# PIC24_sensores_esquem_tico-temp.net
KiCad netlist of a schematic drawn in Altium Designer
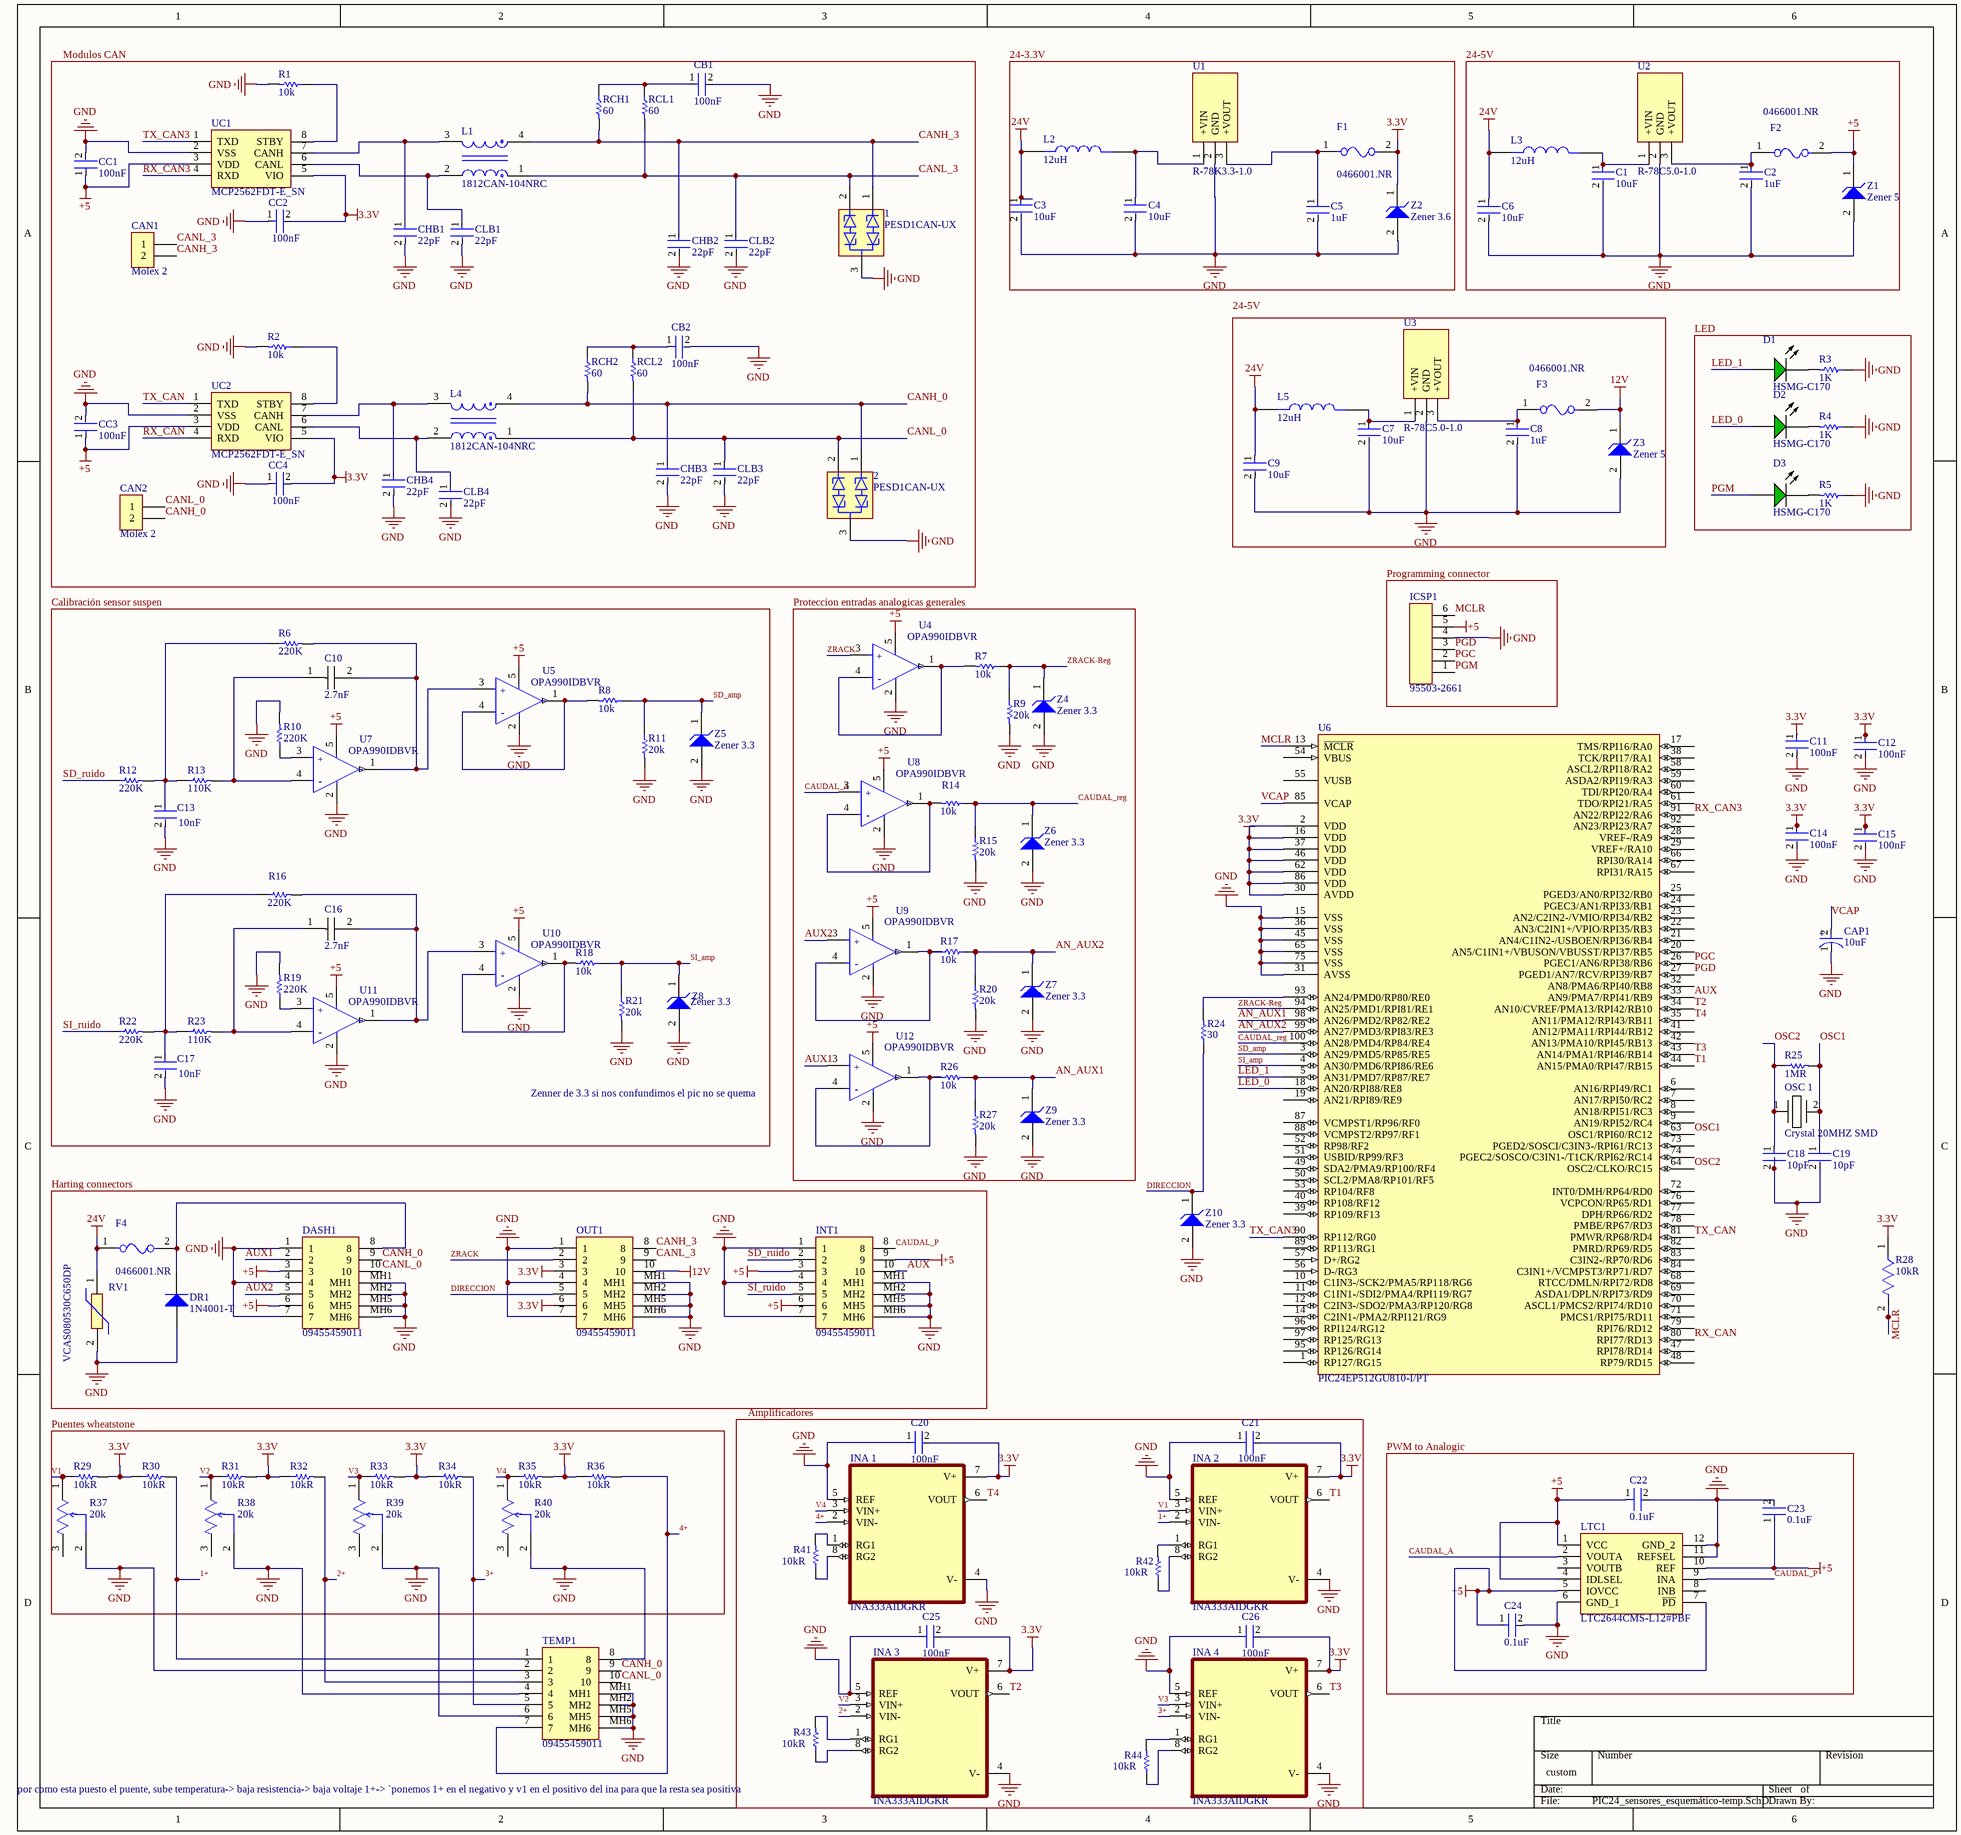
[diagram p0: PIC24_sensores_esquemático-temp.SchDoc]

(export (version "E")
  (design (tool "Eeschema 10.0.6"))
  (components
    (comp (ref "1")
      (value "PESD1CAN-UX")
      (footprint "FP-SOT323-MFG")
      (description "PESD1CAN Series 50 V 9.3 pF SMT CAN bus ESD Protection Diode - SOT-323")
      (libsource (lib "EMEA- Formula Student Team Bizkaia- University of the Basque Country") (part "04d57993b6b7b0f5b3c95ba4f97dea0"))
    )
    (comp (ref "2")
      (value "PESD1CAN-UX")
      (footprint "FP-SOT323-MFG")
      (description "PESD1CAN Series 50 V 9.3 pF SMT CAN bus ESD Protection Diode - SOT-323")
      (libsource (lib "EMEA- Formula Student Team Bizkaia- University of the Basque Country") (part "04d57993b6b7b0f5b3c95ba4f97dea0"))
    )
    (comp (ref "C1")
      (value "10uF")
      (footprint "FP-CL21-IPC_B")
      (description "Cap Ceramic 1uF 25V Y5V -20% to 80% SMD 0805 85°C Embossed T/R")
      (fields (field (name "TOLERANCE") "80%") (field (name "Comment") "CL21F105ZAFNNNF"))
      (libsource (lib "EMEA- Formula Student Team Bizkaia- University of the Basque Country") (part "b4654b650e69147ec39a6b967a45e02"))
    )
    (comp (ref "C2")
      (value "1uF")
      (footprint "FP-CL21-IPC_B")
      (description "Cap Ceramic 1uF 25V Y5V -20% to 80% SMD 0805 85°C Embossed T/R")
      (fields (field (name "TOLERANCE") "80%") (field (name "Comment") "CL21F105ZAFNNNF"))
      (libsource (lib "EMEA- Formula Student Team Bizkaia- University of the Basque Country") (part "b4654b650e69147ec39a6b967a45e02"))
    )
    (comp (ref "C3")
      (value "10uF")
      (footprint "FP-CL21-IPC_B")
      (description "Cap Ceramic 1uF 25V Y5V -20% to 80% SMD 0805 85°C Embossed T/R")
      (fields (field (name "TOLERANCE") "80%") (field (name "Comment") "CL21F105ZAFNNNF"))
      (libsource (lib "EMEA- Formula Student Team Bizkaia- University of the Basque Country") (part "b4654b650e69147ec39a6b967a45e02"))
    )
    (comp (ref "C4")
      (value "10uF")
      (footprint "FP-CL21-IPC_B")
      (description "Cap Ceramic 1uF 25V Y5V -20% to 80% SMD 0805 85°C Embossed T/R")
      (fields (field (name "TOLERANCE") "80%") (field (name "Comment") "CL21F105ZAFNNNF"))
      (libsource (lib "EMEA- Formula Student Team Bizkaia- University of the Basque Country") (part "b4654b650e69147ec39a6b967a45e02"))
    )
    (comp (ref "C5")
      (value "1uF")
      (footprint "FP-CL21-IPC_B")
      (description "Cap Ceramic 1uF 25V Y5V -20% to 80% SMD 0805 85°C Embossed T/R")
      (fields (field (name "TOLERANCE") "80%") (field (name "Comment") "CL21F105ZAFNNNF"))
      (libsource (lib "EMEA- Formula Student Team Bizkaia- University of the Basque Country") (part "b4654b650e69147ec39a6b967a45e02"))
    )
    (comp (ref "C6")
      (value "10uF")
      (footprint "FP-CL21-IPC_B")
      (description "Cap Ceramic 1uF 25V Y5V -20% to 80% SMD 0805 85°C Embossed T/R")
      (fields (field (name "TOLERANCE") "80%") (field (name "Comment") "CL21F105ZAFNNNF"))
      (libsource (lib "EMEA- Formula Student Team Bizkaia- University of the Basque Country") (part "b4654b650e69147ec39a6b967a45e02"))
    )
    (comp (ref "C7")
      (value "10uF")
      (footprint "FP-CL21-IPC_B")
      (description "Cap Ceramic 1uF 25V Y5V -20% to 80% SMD 0805 85°C Embossed T/R")
      (fields (field (name "TOLERANCE") "80%") (field (name "Comment") "CL21F105ZAFNNNF"))
      (libsource (lib "EMEA- Formula Student Team Bizkaia- University of the Basque Country") (part "b4654b650e69147ec39a6b967a45e02"))
    )
    (comp (ref "C8")
      (value "1uF")
      (footprint "FP-CL21-IPC_B")
      (description "Cap Ceramic 1uF 25V Y5V -20% to 80% SMD 0805 85°C Embossed T/R")
      (fields (field (name "TOLERANCE") "80%") (field (name "Comment") "CL21F105ZAFNNNF"))
      (libsource (lib "EMEA- Formula Student Team Bizkaia- University of the Basque Country") (part "b4654b650e69147ec39a6b967a45e02"))
    )
    (comp (ref "C9")
      (value "10uF")
      (footprint "FP-CL21-IPC_B")
      (description "Cap Ceramic 1uF 25V Y5V -20% to 80% SMD 0805 85°C Embossed T/R")
      (fields (field (name "TOLERANCE") "80%") (field (name "Comment") "CL21F105ZAFNNNF"))
      (libsource (lib "EMEA- Formula Student Team Bizkaia- University of the Basque Country") (part "b4654b650e69147ec39a6b967a45e02"))
    )
    (comp (ref "C10")
      (value "2.7nF")
      (footprint "TMK212BJ105KG-T-Footprint-1")
      (description "0805 1 uF 25 V ±10 % X5R Surface Mount Multilayer Ceramic Capacitor")
      (fields (field (name "TOLERANCE") "10%"))
      (libsource (lib "EMEA- Formula Student Team Bizkaia- University of the Basque Country") (part "TMK212BJ105KG-T-Symbol-1"))
    )
    (comp (ref "C11")
      (value "100nF")
      (footprint "FP-CL21-IPC_B")
      (description "Cap Ceramic 1uF 25V Y5V -20% to 80% SMD 0805 85°C Embossed T/R")
      (fields (field (name "TOLERANCE") "80%") (field (name "Comment") "CL21F105ZAFNNNF"))
      (libsource (lib "EMEA- Formula Student Team Bizkaia- University of the Basque Country") (part "b4654b650e69147ec39a6b967a45e02"))
    )
    (comp (ref "C12")
      (value "100nF")
      (footprint "FP-CL21-IPC_B")
      (description "Cap Ceramic 1uF 25V Y5V -20% to 80% SMD 0805 85°C Embossed T/R")
      (fields (field (name "TOLERANCE") "80%") (field (name "Comment") "CL21F105ZAFNNNF"))
      (libsource (lib "EMEA- Formula Student Team Bizkaia- University of the Basque Country") (part "b4654b650e69147ec39a6b967a45e02"))
    )
    (comp (ref "C13")
      (value "10nF")
      (footprint "FP-CL21-IPC_B")
      (description "Cap Ceramic 1uF 25V Y5V -20% to 80% SMD 0805 85°C Embossed T/R")
      (fields (field (name "TOLERANCE") "80%") (field (name "Comment") "CL21F105ZAFNNNF"))
      (libsource (lib "EMEA- Formula Student Team Bizkaia- University of the Basque Country") (part "b4654b650e69147ec39a6b967a45e02"))
    )
    (comp (ref "C14")
      (value "100nF")
      (footprint "FP-CL21-IPC_B")
      (description "Cap Ceramic 1uF 25V Y5V -20% to 80% SMD 0805 85°C Embossed T/R")
      (fields (field (name "TOLERANCE") "80%") (field (name "Comment") "CL21F105ZAFNNNF"))
      (libsource (lib "EMEA- Formula Student Team Bizkaia- University of the Basque Country") (part "b4654b650e69147ec39a6b967a45e02"))
    )
    (comp (ref "C15")
      (value "100nF")
      (footprint "FP-CL21-IPC_B")
      (description "Cap Ceramic 1uF 25V Y5V -20% to 80% SMD 0805 85°C Embossed T/R")
      (fields (field (name "TOLERANCE") "80%") (field (name "Comment") "CL21F105ZAFNNNF"))
      (libsource (lib "EMEA- Formula Student Team Bizkaia- University of the Basque Country") (part "b4654b650e69147ec39a6b967a45e02"))
    )
    (comp (ref "C16")
      (value "2.7nF")
      (footprint "TMK212BJ105KG-T-Footprint-1")
      (description "0805 1 uF 25 V ±10 % X5R Surface Mount Multilayer Ceramic Capacitor")
      (fields (field (name "TOLERANCE") "10%"))
      (libsource (lib "EMEA- Formula Student Team Bizkaia- University of the Basque Country") (part "TMK212BJ105KG-T-Symbol-1"))
    )
    (comp (ref "C17")
      (value "10nF")
      (footprint "FP-CL21-IPC_B")
      (description "Cap Ceramic 1uF 25V Y5V -20% to 80% SMD 0805 85°C Embossed T/R")
      (fields (field (name "TOLERANCE") "80%") (field (name "Comment") "CL21F105ZAFNNNF"))
      (libsource (lib "EMEA- Formula Student Team Bizkaia- University of the Basque Country") (part "b4654b650e69147ec39a6b967a45e02"))
    )
    (comp (ref "C18")
      (value "10pF")
      (footprint "FP-CL21-IPC_B")
      (description "Cap Ceramic 1uF 25V Y5V -20% to 80% SMD 0805 85°C Embossed T/R")
      (fields (field (name "TOLERANCE") "80%") (field (name "Comment") "CL21F105ZAFNNNF"))
      (libsource (lib "EMEA- Formula Student Team Bizkaia- University of the Basque Country") (part "b4654b650e69147ec39a6b967a45e02"))
    )
    (comp (ref "C19")
      (value "10pF")
      (footprint "FP-CL21-IPC_B")
      (description "Cap Ceramic 1uF 25V Y5V -20% to 80% SMD 0805 85°C Embossed T/R")
      (fields (field (name "TOLERANCE") "80%") (field (name "Comment") "CL21F105ZAFNNNF"))
      (libsource (lib "EMEA- Formula Student Team Bizkaia- University of the Basque Country") (part "b4654b650e69147ec39a6b967a45e02"))
    )
    (comp (ref "C20")
      (value "100nF")
      (footprint "FP-CL21-IPC_B")
      (description "Cap Ceramic 1uF 25V Y5V -20% to 80% SMD 0805 85°C Embossed T/R")
      (fields (field (name "TOLERANCE") "80%") (field (name "Comment") "CL21F105ZAFNNNF"))
      (libsource (lib "EMEA- Formula Student Team Bizkaia- University of the Basque Country") (part "b4654b650e69147ec39a6b967a45e02"))
    )
    (comp (ref "C21")
      (value "100nF")
      (footprint "FP-CL21-IPC_B")
      (description "Cap Ceramic 1uF 25V Y5V -20% to 80% SMD 0805 85°C Embossed T/R")
      (fields (field (name "TOLERANCE") "80%") (field (name "Comment") "CL21F105ZAFNNNF"))
      (libsource (lib "EMEA- Formula Student Team Bizkaia- University of the Basque Country") (part "b4654b650e69147ec39a6b967a45e02"))
    )
    (comp (ref "C22")
      (value "0.1uF")
      (footprint "FP-CL21-IPC_B")
      (description "Cap Ceramic 1uF 25V Y5V -20% to 80% SMD 0805 85°C Embossed T/R")
      (fields (field (name "TOLERANCE") "80%") (field (name "Comment") "CL21F105ZAFNNNF"))
      (libsource (lib "EMEA- Formula Student Team Bizkaia- University of the Basque Country") (part "b4654b650e69147ec39a6b967a45e02"))
    )
    (comp (ref "C23")
      (value "0.1uF")
      (footprint "FP-CL21-IPC_B")
      (description "Cap Ceramic 1uF 25V Y5V -20% to 80% SMD 0805 85°C Embossed T/R")
      (fields (field (name "TOLERANCE") "80%") (field (name "Comment") "CL21F105ZAFNNNF"))
      (libsource (lib "EMEA- Formula Student Team Bizkaia- University of the Basque Country") (part "b4654b650e69147ec39a6b967a45e02"))
    )
    (comp (ref "C24")
      (value "0.1uF")
      (footprint "FP-CL21-IPC_B")
      (description "Cap Ceramic 1uF 25V Y5V -20% to 80% SMD 0805 85°C Embossed T/R")
      (fields (field (name "TOLERANCE") "80%") (field (name "Comment") "CL21F105ZAFNNNF"))
      (libsource (lib "EMEA- Formula Student Team Bizkaia- University of the Basque Country") (part "b4654b650e69147ec39a6b967a45e02"))
    )
    (comp (ref "C25")
      (value "100nF")
      (footprint "FP-CL21-IPC_B")
      (description "Cap Ceramic 1uF 25V Y5V -20% to 80% SMD 0805 85°C Embossed T/R")
      (fields (field (name "TOLERANCE") "80%") (field (name "Comment") "CL21F105ZAFNNNF"))
      (libsource (lib "EMEA- Formula Student Team Bizkaia- University of the Basque Country") (part "b4654b650e69147ec39a6b967a45e02"))
    )
    (comp (ref "C26")
      (value "100nF")
      (footprint "FP-CL21-IPC_B")
      (description "Cap Ceramic 1uF 25V Y5V -20% to 80% SMD 0805 85°C Embossed T/R")
      (fields (field (name "TOLERANCE") "80%") (field (name "Comment") "CL21F105ZAFNNNF"))
      (libsource (lib "EMEA- Formula Student Team Bizkaia- University of the Basque Country") (part "b4654b650e69147ec39a6b967a45e02"))
    )
    (comp (ref "CAN1")
      (value "Molex 2")
      (footprint "FP-43650-0228-MFG")
      (description "Conn Wire to Board HDR 2 POS 3mm Solder ST Top Entry Thru-Hole Tray")
      (libsource (lib "EMEA- Formula Student Team Bizkaia- University of the Basque Country") (part "3bc925449376181038e59eaffc5286c"))
    )
    (comp (ref "CAN2")
      (value "Molex 2")
      (footprint "FP-43650-0228-MFG")
      (description "Conn Wire to Board HDR 2 POS 3mm Solder ST Top Entry Thru-Hole Tray")
      (libsource (lib "EMEA- Formula Student Team Bizkaia- University of the Basque Country") (part "3bc925449376181038e59eaffc5286c"))
    )
    (comp (ref "CAP1")
      (value "10uF")
      (footprint "FP-T491B226K016AT-MFG")
      (description "CAP TANT 22UF 10% 16V 1411")
      (fields (field (name "TOLERANCE") "10%") (field (name "VOLTAGE") "16V"))
      (libsource (lib "Altium Content Vault") (part "203bc49f2ac43e59fd269a8c329ed05"))
    )
    (comp (ref "CB1")
      (value "100nF")
      (footprint "FP-CL21-IPC_B")
      (description "Cap Ceramic 1uF 25V Y5V -20% to 80% SMD 0805 85°C Embossed T/R")
      (fields (field (name "TOLERANCE") "80%") (field (name "Comment") "CL21F105ZAFNNNF"))
      (libsource (lib "EMEA- Formula Student Team Bizkaia- University of the Basque Country") (part "b4654b650e69147ec39a6b967a45e02"))
    )
    (comp (ref "CB2")
      (value "100nF")
      (footprint "FP-CL21-IPC_B")
      (description "Cap Ceramic 1uF 25V Y5V -20% to 80% SMD 0805 85°C Embossed T/R")
      (fields (field (name "TOLERANCE") "80%") (field (name "Comment") "CL21F105ZAFNNNF"))
      (libsource (lib "EMEA- Formula Student Team Bizkaia- University of the Basque Country") (part "b4654b650e69147ec39a6b967a45e02"))
    )
    (comp (ref "CC1")
      (value "100nF")
      (footprint "FP-CL21-IPC_B")
      (description "Cap Ceramic 1uF 25V Y5V -20% to 80% SMD 0805 85°C Embossed T/R")
      (fields (field (name "TOLERANCE") "80%") (field (name "Comment") "CL21F105ZAFNNNF"))
      (libsource (lib "EMEA- Formula Student Team Bizkaia- University of the Basque Country") (part "b4654b650e69147ec39a6b967a45e02"))
    )
    (comp (ref "CC2")
      (value "100nF")
      (footprint "FP-CL21-IPC_B")
      (description "Cap Ceramic 1uF 25V Y5V -20% to 80% SMD 0805 85°C Embossed T/R")
      (fields (field (name "TOLERANCE") "80%") (field (name "Comment") "CL21F105ZAFNNNF"))
      (libsource (lib "EMEA- Formula Student Team Bizkaia- University of the Basque Country") (part "b4654b650e69147ec39a6b967a45e02"))
    )
    (comp (ref "CC3")
      (value "100nF")
      (footprint "FP-CL21-IPC_B")
      (description "Cap Ceramic 1uF 25V Y5V -20% to 80% SMD 0805 85°C Embossed T/R")
      (fields (field (name "TOLERANCE") "80%") (field (name "Comment") "CL21F105ZAFNNNF"))
      (libsource (lib "EMEA- Formula Student Team Bizkaia- University of the Basque Country") (part "b4654b650e69147ec39a6b967a45e02"))
    )
    (comp (ref "CC4")
      (value "100nF")
      (footprint "FP-CL21-IPC_B")
      (description "Cap Ceramic 1uF 25V Y5V -20% to 80% SMD 0805 85°C Embossed T/R")
      (fields (field (name "TOLERANCE") "80%") (field (name "Comment") "CL21F105ZAFNNNF"))
      (libsource (lib "EMEA- Formula Student Team Bizkaia- University of the Basque Country") (part "b4654b650e69147ec39a6b967a45e02"))
    )
    (comp (ref "CHB1")
      (value "22pF")
      (footprint "FP-CL21-IPC_B")
      (description "Cap Ceramic 1uF 25V Y5V -20% to 80% SMD 0805 85°C Embossed T/R")
      (fields (field (name "TOLERANCE") "80%") (field (name "Comment") "CL21F105ZAFNNNF"))
      (libsource (lib "EMEA- Formula Student Team Bizkaia- University of the Basque Country") (part "b4654b650e69147ec39a6b967a45e02"))
    )
    (comp (ref "CHB2")
      (value "22pF")
      (footprint "FP-CL21-IPC_B")
      (description "Cap Ceramic 1uF 25V Y5V -20% to 80% SMD 0805 85°C Embossed T/R")
      (fields (field (name "TOLERANCE") "80%") (field (name "Comment") "CL21F105ZAFNNNF"))
      (libsource (lib "EMEA- Formula Student Team Bizkaia- University of the Basque Country") (part "b4654b650e69147ec39a6b967a45e02"))
    )
    (comp (ref "CHB3")
      (value "22pF")
      (footprint "FP-CL21-IPC_B")
      (description "Cap Ceramic 1uF 25V Y5V -20% to 80% SMD 0805 85°C Embossed T/R")
      (fields (field (name "TOLERANCE") "80%") (field (name "Comment") "CL21F105ZAFNNNF"))
      (libsource (lib "EMEA- Formula Student Team Bizkaia- University of the Basque Country") (part "b4654b650e69147ec39a6b967a45e02"))
    )
    (comp (ref "CHB4")
      (value "22pF")
      (footprint "FP-CL21-IPC_B")
      (description "Cap Ceramic 1uF 25V Y5V -20% to 80% SMD 0805 85°C Embossed T/R")
      (fields (field (name "TOLERANCE") "80%") (field (name "Comment") "CL21F105ZAFNNNF"))
      (libsource (lib "EMEA- Formula Student Team Bizkaia- University of the Basque Country") (part "b4654b650e69147ec39a6b967a45e02"))
    )
    (comp (ref "CLB1")
      (value "22pF")
      (footprint "FP-CL21-IPC_B")
      (description "Cap Ceramic 1uF 25V Y5V -20% to 80% SMD 0805 85°C Embossed T/R")
      (fields (field (name "TOLERANCE") "80%") (field (name "Comment") "CL21F105ZAFNNNF"))
      (libsource (lib "EMEA- Formula Student Team Bizkaia- University of the Basque Country") (part "b4654b650e69147ec39a6b967a45e02"))
    )
    (comp (ref "CLB2")
      (value "22pF")
      (footprint "FP-CL21-IPC_B")
      (description "Cap Ceramic 1uF 25V Y5V -20% to 80% SMD 0805 85°C Embossed T/R")
      (fields (field (name "TOLERANCE") "80%") (field (name "Comment") "CL21F105ZAFNNNF"))
      (libsource (lib "EMEA- Formula Student Team Bizkaia- University of the Basque Country") (part "b4654b650e69147ec39a6b967a45e02"))
    )
    (comp (ref "CLB3")
      (value "22pF")
      (footprint "FP-CL21-IPC_B")
      (description "Cap Ceramic 1uF 25V Y5V -20% to 80% SMD 0805 85°C Embossed T/R")
      (fields (field (name "TOLERANCE") "80%") (field (name "Comment") "CL21F105ZAFNNNF"))
      (libsource (lib "EMEA- Formula Student Team Bizkaia- University of the Basque Country") (part "b4654b650e69147ec39a6b967a45e02"))
    )
    (comp (ref "CLB4")
      (value "22pF")
      (footprint "FP-CL21-IPC_B")
      (description "Cap Ceramic 1uF 25V Y5V -20% to 80% SMD 0805 85°C Embossed T/R")
      (fields (field (name "TOLERANCE") "80%") (field (name "Comment") "CL21F105ZAFNNNF"))
      (libsource (lib "EMEA- Formula Student Team Bizkaia- University of the Basque Country") (part "b4654b650e69147ec39a6b967a45e02"))
    )
    (comp (ref "D1")
      (value "HSMG-C170")
      (footprint "AVAG-HSMX-C170_V")
      (description "Led 570NM Green Diff 0805 SMD")
      (libsource (lib "EMEA- Formula Student Team Bizkaia- University of the Basque Country") (part "LED_GREEN_A1K2-2"))
    )
    (comp (ref "D2")
      (value "HSMG-C170")
      (footprint "AVAG-HSMX-C170_V")
      (description "Led 570NM Green Diff 0805 SMD")
      (libsource (lib "EMEA- Formula Student Team Bizkaia- University of the Basque Country") (part "LED_GREEN_A1K2-2"))
    )
    (comp (ref "D3")
      (value "HSMG-C170")
      (footprint "AVAG-HSMX-C170_V")
      (description "Led 570NM Green Diff 0805 SMD")
      (libsource (lib "EMEA- Formula Student Team Bizkaia- University of the Basque Country") (part "LED_GREEN_A1K2-2"))
    )
    (comp (ref "DASH1")
      (value "09455459011")
      (footprint "09455459011")
      (description "Harting Pushpull V4 Signal, 10Pins, Panel Side Insert For Angled Solder Termination")
      (libsource (lib "EMEA- Formula Student Team Bizkaia- University of the Basque Country") (part "09455459011-Symbol-1"))
    )
    (comp (ref "DR1")
      (value "1N4001-T")
      (footprint "DIOD-DO-41-P-2_V")
      (description "Diode Standard Recovery Rectifier 50V 1A 2-Pin DO-41 T/R")
      (libsource (lib "EMEA- Formula Student Team Bizkaia- University of the Basque Country") (part "DIOD-D-A1K2-2"))
    )
    (comp (ref "F1")
      (value "0466001.NR")
      (footprint "FP-0466-MFG")
      (description "Fuse Chip Very Fast Acting 1A 63V SMD Solder Pad 1206 T/R CSA")
      (libsource (lib "EMEA- Formula Student Team Bizkaia- University of the Basque Country") (part "5bcf9b9f640e542cf0359d10258e979"))
    )
    (comp (ref "F2")
      (value "0466001.NR")
      (footprint "FP-0466-MFG")
      (description "Fuse Chip Very Fast Acting 1A 63V SMD Solder Pad 1206 T/R CSA")
      (libsource (lib "EMEA- Formula Student Team Bizkaia- University of the Basque Country") (part "5bcf9b9f640e542cf0359d10258e979"))
    )
    (comp (ref "F3")
      (value "0466001.NR")
      (footprint "FP-0466-MFG")
      (description "Fuse Chip Very Fast Acting 1A 63V SMD Solder Pad 1206 T/R CSA")
      (libsource (lib "EMEA- Formula Student Team Bizkaia- University of the Basque Country") (part "5bcf9b9f640e542cf0359d10258e979"))
    )
    (comp (ref "F4")
      (value "0466001.NR")
      (footprint "FP-0466-MFG")
      (description "Fuse Chip Very Fast Acting 1A 63V SMD Solder Pad 1206 T/R CSA")
      (libsource (lib "EMEA- Formula Student Team Bizkaia- University of the Basque Country") (part "5bcf9b9f640e542cf0359d10258e979"))
    )
    (comp (ref "ICSP1")
      (value "95503-2661")
      (footprint "FP-95503-2661-MFG")
      (description "Modular Jack, Vertical, Top Entry, Through Hole, 6/6, No Key Version, Tray")
      (libsource (lib "EMEA- Formula Student Team Bizkaia- University of the Basque Country") (part "8e316149632ed9de2284434d52fa554"))
    )
    (comp (ref "INA 1")
      (value "INA333AIDGKR")
      (footprint "SOP65P490X110-8N")
      (description "Low-Power, Zero-Drift, Precision Instrumentation Amplifier 8-VSSOP -40 to 125")
      (fields (field (name "MF") "Texas Instruments") (field (name "DIGI-KEY_PART_NUMBER") "296-23564-1-ND"))
      (libsource (lib "EMEA- Formula Student Team Bizkaia- University of the Basque Country") (part "INA333AIDGKR"))
    )
    (comp (ref "INA 2")
      (value "INA333AIDGKR")
      (footprint "SOP65P490X110-8N")
      (description "Low-Power, Zero-Drift, Precision Instrumentation Amplifier 8-VSSOP -40 to 125")
      (fields (field (name "MF") "Texas Instruments") (field (name "DIGI-KEY_PART_NUMBER") "296-23564-1-ND"))
      (libsource (lib "EMEA- Formula Student Team Bizkaia- University of the Basque Country") (part "INA333AIDGKR"))
    )
    (comp (ref "INA 3")
      (value "INA333AIDGKR")
      (footprint "SOP65P490X110-8N")
      (description "Low-Power, Zero-Drift, Precision Instrumentation Amplifier 8-VSSOP -40 to 125")
      (fields (field (name "MF") "Texas Instruments") (field (name "DIGI-KEY_PART_NUMBER") "296-23564-1-ND"))
      (libsource (lib "EMEA- Formula Student Team Bizkaia- University of the Basque Country") (part "INA333AIDGKR"))
    )
    (comp (ref "INA 4")
      (value "INA333AIDGKR")
      (footprint "SOP65P490X110-8N")
      (description "Low-Power, Zero-Drift, Precision Instrumentation Amplifier 8-VSSOP -40 to 125")
      (fields (field (name "MF") "Texas Instruments") (field (name "DIGI-KEY_PART_NUMBER") "296-23564-1-ND"))
      (libsource (lib "EMEA- Formula Student Team Bizkaia- University of the Basque Country") (part "INA333AIDGKR"))
    )
    (comp (ref "INT1")
      (value "09455459011")
      (footprint "09455459011")
      (description "Harting Pushpull V4 Signal, 10Pins, Panel Side Insert For Angled Solder Termination")
      (libsource (lib "EMEA- Formula Student Team Bizkaia- University of the Basque Country") (part "09455459011-Symbol-1"))
    )
    (comp (ref "L1")
      (value "1812CAN-104NRC")
      (footprint "FP-1812CAN-MFG")
      (description "Common Mode Choke, 30% tol, SMT, RoHS, halogen-free")
      (libsource (lib "EMEA- Formula Student Team Bizkaia- University of the Basque Country") (part "990f770e997bc1827b8220d62ec964c"))
    )
    (comp (ref "L2")
      (value "12uH")
      (footprint "IND_RLS-126")
      (description "Line Inductors for RECOM Power Supply")
      (fields (field (name "MF") "Recom Power") (field (name "MP") "RLS-126"))
      (libsource (lib "EMEA- Formula Student Team Bizkaia- University of the Basque Country") (part "RLS-126"))
    )
    (comp (ref "L3")
      (value "12uH")
      (footprint "IND_RLS-126")
      (description "Line Inductors for RECOM Power Supply")
      (fields (field (name "MF") "Recom Power") (field (name "MP") "RLS-126"))
      (libsource (lib "EMEA- Formula Student Team Bizkaia- University of the Basque Country") (part "RLS-126"))
    )
    (comp (ref "L4")
      (value "1812CAN-104NRC")
      (footprint "FP-1812CAN-MFG")
      (description "Common Mode Choke, 30% tol, SMT, RoHS, halogen-free")
      (libsource (lib "EMEA- Formula Student Team Bizkaia- University of the Basque Country") (part "990f770e997bc1827b8220d62ec964c"))
    )
    (comp (ref "L5")
      (value "12uH")
      (footprint "IND_RLS-126")
      (description "Line Inductors for RECOM Power Supply")
      (fields (field (name "MF") "Recom Power") (field (name "MP") "RLS-126"))
      (libsource (lib "EMEA- Formula Student Team Bizkaia- University of the Basque Country") (part "RLS-126"))
    )
    (comp (ref "LTC1")
      (value "LTC2644CMS-L12#PBF")
      (footprint "SamacSys:SOP65P490X110-12N")
      (description "Integrated Circuit")
      (fields (field (name "MOUSER PART NUMBER") "584-C2644CMS-L12PBF"))
      (libsource (lib "*") (part "LTC2644CMS-L12#PBF"))
    )
    (comp (ref "OSC 1")
      (value "Crystal 20MHZ SMD")
      (footprint "LFXTAL003181-Footprint-1")
      (description "LFXTAL003181 - Crystal 20MHZ 16PF 2-PIN HC-49/4H Smx Bulk")
      (libsource (lib "EMEA- Formula Student Team Bizkaia- University of the Basque Country") (part "LFXTAL003181-Symbol-1"))
    )
    (comp (ref "OUT1")
      (value "09455459011")
      (footprint "09455459011")
      (description "Harting Pushpull V4 Signal, 10Pins, Panel Side Insert For Angled Solder Termination")
      (libsource (lib "EMEA- Formula Student Team Bizkaia- University of the Basque Country") (part "09455459011-Symbol-1"))
    )
    (comp (ref "R1")
      (value "10k")
      (footprint "RESC2013X60X35LL10T20")
      (description "SMD Chip Resistor, 10 kOhm, ± 1%, 125 mW, 0805 [2012 Metric], Thick Film, General Purpose")
      (fields (field (name "TOLERANCE") "1%") (field (name "Comment") "RC0805FR-0710KL"))
      (libsource (lib "EMEA- Formula Student Team Bizkaia- University of the Basque Country") (part "RES-2"))
    )
    (comp (ref "R2")
      (value "10k")
      (footprint "RESC2013X60X35LL10T20")
      (description "SMD Chip Resistor, 10 kOhm, ± 1%, 125 mW, 0805 [2012 Metric], Thick Film, General Purpose")
      (fields (field (name "TOLERANCE") "1%") (field (name "Comment") "RC0805FR-0710KL"))
      (libsource (lib "EMEA- Formula Student Team Bizkaia- University of the Basque Country") (part "RES-2"))
    )
    (comp (ref "R3")
      (value "1K")
      (footprint "RESC2013X60X35LL10T20")
      (description "SMD Chip Resistor, 10 kOhm, ± 1%, 125 mW, 0805 [2012 Metric], Thick Film, General Purpose")
      (fields (field (name "TOLERANCE") "1%") (field (name "Comment") "RC0805FR-0710KL"))
      (libsource (lib "EMEA- Formula Student Team Bizkaia- University of the Basque Country") (part "RES-2"))
    )
    (comp (ref "R4")
      (value "1K")
      (footprint "RESC2013X60X35LL10T20")
      (description "SMD Chip Resistor, 10 kOhm, ± 1%, 125 mW, 0805 [2012 Metric], Thick Film, General Purpose")
      (fields (field (name "TOLERANCE") "1%") (field (name "Comment") "RC0805FR-0710KL"))
      (libsource (lib "EMEA- Formula Student Team Bizkaia- University of the Basque Country") (part "RES-2"))
    )
    (comp (ref "R5")
      (value "1K")
      (footprint "RESC2013X60X35LL10T20")
      (description "SMD Chip Resistor, 10 kOhm, ± 1%, 125 mW, 0805 [2012 Metric], Thick Film, General Purpose")
      (fields (field (name "TOLERANCE") "1%") (field (name "Comment") "RC0805FR-0710KL"))
      (libsource (lib "EMEA- Formula Student Team Bizkaia- University of the Basque Country") (part "RES-2"))
    )
    (comp (ref "R6")
      (value "220K")
      (footprint "FP-MCU0805-MFG")
      (description "SMD Chip Resistor, 10 kOhm, ± 0.1%, 125 mW, 0805 [2012 Metric], Thin Film, Precision")
      (fields (field (name "TOLERANCE") "0.1%") (field (name "Comment") "MCU08050D1002BP100"))
      (libsource (lib "EMEA- Formula Student Team Bizkaia- University of the Basque Country") (part "1029c3af85768c4190bb7ad29bc67b5"))
    )
    (comp (ref "R7")
      (value "10k")
      (footprint "RESC2013X60X35LL10T20")
      (description "SMD Chip Resistor, 10 kOhm, ± 1%, 125 mW, 0805 [2012 Metric], Thick Film, General Purpose")
      (fields (field (name "TOLERANCE") "1%") (field (name "Comment") "RC0805FR-0710KL"))
      (libsource (lib "EMEA- Formula Student Team Bizkaia- University of the Basque Country") (part "RES-2"))
    )
    (comp (ref "R8")
      (value "10k")
      (footprint "RESC2013X60X35LL10T20")
      (description "SMD Chip Resistor, 10 kOhm, ± 1%, 125 mW, 0805 [2012 Metric], Thick Film, General Purpose")
      (fields (field (name "TOLERANCE") "1%") (field (name "Comment") "RC0805FR-0710KL"))
      (libsource (lib "EMEA- Formula Student Team Bizkaia- University of the Basque Country") (part "RES-2"))
    )
    (comp (ref "R9")
      (value "20k")
      (footprint "RESC2013X60X35LL10T20")
      (description "SMD Chip Resistor, 10 kOhm, ± 1%, 125 mW, 0805 [2012 Metric], Thick Film, General Purpose")
      (fields (field (name "TOLERANCE") "1%") (field (name "Comment") "RC0805FR-0710KL"))
      (libsource (lib "EMEA- Formula Student Team Bizkaia- University of the Basque Country") (part "RES-2"))
    )
    (comp (ref "R10")
      (value "220K")
      (footprint "FP-MCU0805-MFG")
      (description "SMD Chip Resistor, 10 kOhm, ± 0.1%, 125 mW, 0805 [2012 Metric], Thin Film, Precision")
      (fields (field (name "TOLERANCE") "0.1%") (field (name "Comment") "MCU08050D1002BP100"))
      (libsource (lib "EMEA- Formula Student Team Bizkaia- University of the Basque Country") (part "1029c3af85768c4190bb7ad29bc67b5"))
    )
    (comp (ref "R11")
      (value "20k")
      (footprint "RESC2013X60X35LL10T20")
      (description "SMD Chip Resistor, 10 kOhm, ± 1%, 125 mW, 0805 [2012 Metric], Thick Film, General Purpose")
      (fields (field (name "TOLERANCE") "1%") (field (name "Comment") "RC0805FR-0710KL"))
      (libsource (lib "EMEA- Formula Student Team Bizkaia- University of the Basque Country") (part "RES-2"))
    )
    (comp (ref "R12")
      (value "220K")
      (footprint "FP-MCU0805-MFG")
      (description "SMD Chip Resistor, 10 kOhm, ± 0.1%, 125 mW, 0805 [2012 Metric], Thin Film, Precision")
      (fields (field (name "TOLERANCE") "0.1%") (field (name "Comment") "MCU08050D1002BP100"))
      (libsource (lib "EMEA- Formula Student Team Bizkaia- University of the Basque Country") (part "1029c3af85768c4190bb7ad29bc67b5"))
    )
    (comp (ref "R13")
      (value "110K")
      (footprint "FP-MCU0805-MFG")
      (description "SMD Chip Resistor, 10 kOhm, ± 0.1%, 125 mW, 0805 [2012 Metric], Thin Film, Precision")
      (fields (field (name "TOLERANCE") "0.1%") (field (name "Comment") "MCU08050D1002BP100"))
      (libsource (lib "EMEA- Formula Student Team Bizkaia- University of the Basque Country") (part "1029c3af85768c4190bb7ad29bc67b5"))
    )
    (comp (ref "R14")
      (value "10k")
      (footprint "RESC2013X60X35LL10T20")
      (description "SMD Chip Resistor, 10 kOhm, ± 1%, 125 mW, 0805 [2012 Metric], Thick Film, General Purpose")
      (fields (field (name "TOLERANCE") "1%") (field (name "Comment") "RC0805FR-0710KL"))
      (libsource (lib "EMEA- Formula Student Team Bizkaia- University of the Basque Country") (part "RES-2"))
    )
    (comp (ref "R15")
      (value "20k")
      (footprint "RESC2013X60X35LL10T20")
      (description "SMD Chip Resistor, 10 kOhm, ± 1%, 125 mW, 0805 [2012 Metric], Thick Film, General Purpose")
      (fields (field (name "TOLERANCE") "1%") (field (name "Comment") "RC0805FR-0710KL"))
      (libsource (lib "EMEA- Formula Student Team Bizkaia- University of the Basque Country") (part "RES-2"))
    )
    (comp (ref "R16")
      (value "220K")
      (footprint "FP-MCU0805-MFG")
      (description "SMD Chip Resistor, 10 kOhm, ± 0.1%, 125 mW, 0805 [2012 Metric], Thin Film, Precision")
      (fields (field (name "TOLERANCE") "0.1%") (field (name "Comment") "MCU08050D1002BP100"))
      (libsource (lib "EMEA- Formula Student Team Bizkaia- University of the Basque Country") (part "1029c3af85768c4190bb7ad29bc67b5"))
    )
    (comp (ref "R17")
      (value "10k")
      (footprint "RESC2013X60X35LL10T20")
      (description "SMD Chip Resistor, 10 kOhm, ± 1%, 125 mW, 0805 [2012 Metric], Thick Film, General Purpose")
      (fields (field (name "TOLERANCE") "1%") (field (name "Comment") "RC0805FR-0710KL"))
      (libsource (lib "EMEA- Formula Student Team Bizkaia- University of the Basque Country") (part "RES-2"))
    )
    (comp (ref "R18")
      (value "10k")
      (footprint "RESC2013X60X35LL10T20")
      (description "SMD Chip Resistor, 10 kOhm, ± 1%, 125 mW, 0805 [2012 Metric], Thick Film, General Purpose")
      (fields (field (name "TOLERANCE") "1%") (field (name "Comment") "RC0805FR-0710KL"))
      (libsource (lib "EMEA- Formula Student Team Bizkaia- University of the Basque Country") (part "RES-2"))
    )
    (comp (ref "R19")
      (value "220K")
      (footprint "FP-MCU0805-MFG")
      (description "SMD Chip Resistor, 10 kOhm, ± 0.1%, 125 mW, 0805 [2012 Metric], Thin Film, Precision")
      (fields (field (name "TOLERANCE") "0.1%") (field (name "Comment") "MCU08050D1002BP100"))
      (libsource (lib "EMEA- Formula Student Team Bizkaia- University of the Basque Country") (part "1029c3af85768c4190bb7ad29bc67b5"))
    )
    (comp (ref "R20")
      (value "20k")
      (footprint "RESC2013X60X35LL10T20")
      (description "SMD Chip Resistor, 10 kOhm, ± 1%, 125 mW, 0805 [2012 Metric], Thick Film, General Purpose")
      (fields (field (name "TOLERANCE") "1%") (field (name "Comment") "RC0805FR-0710KL"))
      (libsource (lib "EMEA- Formula Student Team Bizkaia- University of the Basque Country") (part "RES-2"))
    )
    (comp (ref "R21")
      (value "20k")
      (footprint "RESC2013X60X35LL10T20")
      (description "SMD Chip Resistor, 10 kOhm, ± 1%, 125 mW, 0805 [2012 Metric], Thick Film, General Purpose")
      (fields (field (name "TOLERANCE") "1%") (field (name "Comment") "RC0805FR-0710KL"))
      (libsource (lib "EMEA- Formula Student Team Bizkaia- University of the Basque Country") (part "RES-2"))
    )
    (comp (ref "R22")
      (value "220K")
      (footprint "FP-MCU0805-MFG")
      (description "SMD Chip Resistor, 10 kOhm, ± 0.1%, 125 mW, 0805 [2012 Metric], Thin Film, Precision")
      (fields (field (name "TOLERANCE") "0.1%") (field (name "Comment") "MCU08050D1002BP100"))
      (libsource (lib "EMEA- Formula Student Team Bizkaia- University of the Basque Country") (part "1029c3af85768c4190bb7ad29bc67b5"))
    )
    (comp (ref "R23")
      (value "110K")
      (footprint "FP-MCU0805-MFG")
      (description "SMD Chip Resistor, 10 kOhm, ± 0.1%, 125 mW, 0805 [2012 Metric], Thin Film, Precision")
      (fields (field (name "TOLERANCE") "0.1%") (field (name "Comment") "MCU08050D1002BP100"))
      (libsource (lib "EMEA- Formula Student Team Bizkaia- University of the Basque Country") (part "1029c3af85768c4190bb7ad29bc67b5"))
    )
    (comp (ref "R24")
      (value "30")
      (footprint "RESC2013X60X35LL10T20")
      (description "SMD Chip Resistor, 10 kOhm, ± 1%, 125 mW, 0805 [2012 Metric], Thick Film, General Purpose")
      (fields (field (name "TOLERANCE") "1%") (field (name "Comment") "RC0805FR-0710KL"))
      (libsource (lib "EMEA- Formula Student Team Bizkaia- University of the Basque Country") (part "RES-2"))
    )
    (comp (ref "R25")
      (value "1MR")
      (footprint "RESC2013X60X35LL10T20")
      (description "SMD Chip Resistor, 10 kOhm, ± 1%, 125 mW, 0805 [2012 Metric], Thick Film, General Purpose")
      (fields (field (name "TOLERANCE") "1%") (field (name "Comment") "RC0805FR-0710KL"))
      (libsource (lib "EMEA- Formula Student Team Bizkaia- University of the Basque Country") (part "RES-2"))
    )
    (comp (ref "R26")
      (value "10k")
      (footprint "RESC2013X60X35LL10T20")
      (description "SMD Chip Resistor, 10 kOhm, ± 1%, 125 mW, 0805 [2012 Metric], Thick Film, General Purpose")
      (fields (field (name "TOLERANCE") "1%") (field (name "Comment") "RC0805FR-0710KL"))
      (libsource (lib "EMEA- Formula Student Team Bizkaia- University of the Basque Country") (part "RES-2"))
    )
    (comp (ref "R27")
      (value "20k")
      (footprint "RESC2013X60X35LL10T20")
      (description "SMD Chip Resistor, 10 kOhm, ± 1%, 125 mW, 0805 [2012 Metric], Thick Film, General Purpose")
      (fields (field (name "TOLERANCE") "1%") (field (name "Comment") "RC0805FR-0710KL"))
      (libsource (lib "EMEA- Formula Student Team Bizkaia- University of the Basque Country") (part "RES-2"))
    )
    (comp (ref "R28")
      (value "10kR")
      (footprint "FP-MCU0805-MFG")
      (description "SMD Chip Resistor, 10 kOhm, ± 0.1%, 125 mW, 0805 [2012 Metric], Thin Film, Precision")
      (fields (field (name "TOLERANCE") "0.1%") (field (name "Comment") "MCU08050D1002BP100"))
      (libsource (lib "") (part "1029c3af85768c4190bb7ad29bc67b5_1"))
    )
    (comp (ref "R29")
      (value "10kR")
      (footprint "RESC2013X60X35LL10T20")
      (description "SMD Chip Resistor, 10 kOhm, ± 1%, 125 mW, 0805 [2012 Metric], Thick Film, General Purpose")
      (fields (field (name "TOLERANCE") "1%") (field (name "Comment") "RC0805FR-0710KL"))
      (libsource (lib "EMEA- Formula Student Team Bizkaia- University of the Basque Country") (part "RES-2"))
    )
    (comp (ref "R30")
      (value "10kR")
      (footprint "RESC2013X60X35LL10T20")
      (description "SMD Chip Resistor, 10 kOhm, ± 1%, 125 mW, 0805 [2012 Metric], Thick Film, General Purpose")
      (fields (field (name "TOLERANCE") "1%") (field (name "Comment") "RC0805FR-0710KL"))
      (libsource (lib "EMEA- Formula Student Team Bizkaia- University of the Basque Country") (part "RES-2"))
    )
    (comp (ref "R31")
      (value "10kR")
      (footprint "RESC2013X60X35LL10T20")
      (description "SMD Chip Resistor, 10 kOhm, ± 1%, 125 mW, 0805 [2012 Metric], Thick Film, General Purpose")
      (fields (field (name "TOLERANCE") "1%") (field (name "Comment") "RC0805FR-0710KL"))
      (libsource (lib "EMEA- Formula Student Team Bizkaia- University of the Basque Country") (part "RES-2"))
    )
    (comp (ref "R32")
      (value "10kR")
      (footprint "RESC2013X60X35LL10T20")
      (description "SMD Chip Resistor, 10 kOhm, ± 1%, 125 mW, 0805 [2012 Metric], Thick Film, General Purpose")
      (fields (field (name "TOLERANCE") "1%") (field (name "Comment") "RC0805FR-0710KL"))
      (libsource (lib "EMEA- Formula Student Team Bizkaia- University of the Basque Country") (part "RES-2"))
    )
    (comp (ref "R33")
      (value "10kR")
      (footprint "RESC2013X60X35LL10T20")
      (description "SMD Chip Resistor, 10 kOhm, ± 1%, 125 mW, 0805 [2012 Metric], Thick Film, General Purpose")
      (fields (field (name "TOLERANCE") "1%") (field (name "Comment") "RC0805FR-0710KL"))
      (libsource (lib "EMEA- Formula Student Team Bizkaia- University of the Basque Country") (part "RES-2"))
    )
    (comp (ref "R34")
      (value "10kR")
      (footprint "RESC2013X60X35LL10T20")
      (description "SMD Chip Resistor, 10 kOhm, ± 1%, 125 mW, 0805 [2012 Metric], Thick Film, General Purpose")
      (fields (field (name "TOLERANCE") "1%") (field (name "Comment") "RC0805FR-0710KL"))
      (libsource (lib "EMEA- Formula Student Team Bizkaia- University of the Basque Country") (part "RES-2"))
    )
    (comp (ref "R35")
      (value "10kR")
      (footprint "RESC2013X60X35LL10T20")
      (description "SMD Chip Resistor, 10 kOhm, ± 1%, 125 mW, 0805 [2012 Metric], Thick Film, General Purpose")
      (fields (field (name "TOLERANCE") "1%") (field (name "Comment") "RC0805FR-0710KL"))
      (libsource (lib "EMEA- Formula Student Team Bizkaia- University of the Basque Country") (part "RES-2"))
    )
    (comp (ref "R36")
      (value "10kR")
      (footprint "RESC2013X60X35LL10T20")
      (description "SMD Chip Resistor, 10 kOhm, ± 1%, 125 mW, 0805 [2012 Metric], Thick Film, General Purpose")
      (fields (field (name "TOLERANCE") "1%") (field (name "Comment") "RC0805FR-0710KL"))
      (libsource (lib "EMEA- Formula Student Team Bizkaia- University of the Basque Country") (part "RES-2"))
    )
    (comp (ref "R37")
      (value "20k")
      (footprint "FP-3296W-MFG")
      (description "Trimmer Potentiometer 2k Ohm 10% 1/2 Watt 25 Turn 2.19mm Pin Through Hole")
      (fields (field (name "TOLERANCE") "10%") (field (name "Comment") "3296W-1-202LF"))
      (libsource (lib "EMEA- Formula Student Team Bizkaia- University of the Basque Country") (part "81a8d1f2e6c155a1fa928b358d1a42a"))
    )
    (comp (ref "R38")
      (value "20k")
      (footprint "FP-3296W-MFG")
      (description "Trimmer Potentiometer 2k Ohm 10% 1/2 Watt 25 Turn 2.19mm Pin Through Hole")
      (fields (field (name "TOLERANCE") "10%") (field (name "Comment") "3296W-1-202LF"))
      (libsource (lib "EMEA- Formula Student Team Bizkaia- University of the Basque Country") (part "81a8d1f2e6c155a1fa928b358d1a42a"))
    )
    (comp (ref "R39")
      (value "20k")
      (footprint "FP-3296W-MFG")
      (description "Trimmer Potentiometer 2k Ohm 10% 1/2 Watt 25 Turn 2.19mm Pin Through Hole")
      (fields (field (name "TOLERANCE") "10%") (field (name "Comment") "3296W-1-202LF"))
      (libsource (lib "EMEA- Formula Student Team Bizkaia- University of the Basque Country") (part "81a8d1f2e6c155a1fa928b358d1a42a"))
    )
    (comp (ref "R40")
      (value "20k")
      (footprint "FP-3296W-MFG")
      (description "Trimmer Potentiometer 2k Ohm 10% 1/2 Watt 25 Turn 2.19mm Pin Through Hole")
      (fields (field (name "TOLERANCE") "10%") (field (name "Comment") "3296W-1-202LF"))
      (libsource (lib "EMEA- Formula Student Team Bizkaia- University of the Basque Country") (part "81a8d1f2e6c155a1fa928b358d1a42a"))
    )
    (comp (ref "R41")
      (value "10kR")
      (footprint "RESC2013X60X35LL10T20")
      (description "SMD Chip Resistor, 10 kOhm, ± 1%, 125 mW, 0805 [2012 Metric], Thick Film, General Purpose")
      (fields (field (name "TOLERANCE") "1%") (field (name "Comment") "RC0805FR-0710KL"))
      (libsource (lib "EMEA- Formula Student Team Bizkaia- University of the Basque Country") (part "RES-2"))
    )
    (comp (ref "R42")
      (value "10kR")
      (footprint "RESC2013X60X35LL10T20")
      (description "SMD Chip Resistor, 10 kOhm, ± 1%, 125 mW, 0805 [2012 Metric], Thick Film, General Purpose")
      (fields (field (name "TOLERANCE") "1%") (field (name "Comment") "RC0805FR-0710KL"))
      (libsource (lib "EMEA- Formula Student Team Bizkaia- University of the Basque Country") (part "RES-2"))
    )
    (comp (ref "R43")
      (value "10kR")
      (footprint "RESC2013X60X35LL10T20")
      (description "SMD Chip Resistor, 10 kOhm, ± 1%, 125 mW, 0805 [2012 Metric], Thick Film, General Purpose")
      (fields (field (name "TOLERANCE") "1%") (field (name "Comment") "RC0805FR-0710KL"))
      (libsource (lib "EMEA- Formula Student Team Bizkaia- University of the Basque Country") (part "RES-2"))
    )
    (comp (ref "R44")
      (value "10kR")
      (footprint "RESC2013X60X35LL10T20")
      (description "SMD Chip Resistor, 10 kOhm, ± 1%, 125 mW, 0805 [2012 Metric], Thick Film, General Purpose")
      (fields (field (name "TOLERANCE") "1%") (field (name "Comment") "RC0805FR-0710KL"))
      (libsource (lib "EMEA- Formula Student Team Bizkaia- University of the Basque Country") (part "RES-2"))
    )
    (comp (ref "RCH1")
      (value "60")
      (footprint "RESC2013X60X35LL10T20")
      (description "SMD Chip Resistor, 10 kOhm, ± 1%, 125 mW, 0805 [2012 Metric], Thick Film, General Purpose")
      (fields (field (name "TOLERANCE") "1%") (field (name "Comment") "RC0805FR-0710KL"))
      (libsource (lib "EMEA- Formula Student Team Bizkaia- University of the Basque Country") (part "RES-2"))
    )
    (comp (ref "RCH2")
      (value "60")
      (footprint "RESC2013X60X35LL10T20")
      (description "SMD Chip Resistor, 10 kOhm, ± 1%, 125 mW, 0805 [2012 Metric], Thick Film, General Purpose")
      (fields (field (name "TOLERANCE") "1%") (field (name "Comment") "RC0805FR-0710KL"))
      (libsource (lib "EMEA- Formula Student Team Bizkaia- University of the Basque Country") (part "RES-2"))
    )
    (comp (ref "RCL1")
      (value "60")
      (footprint "RESC2013X60X35LL10T20")
      (description "SMD Chip Resistor, 10 kOhm, ± 1%, 125 mW, 0805 [2012 Metric], Thick Film, General Purpose")
      (fields (field (name "TOLERANCE") "1%") (field (name "Comment") "RC0805FR-0710KL"))
      (libsource (lib "EMEA- Formula Student Team Bizkaia- University of the Basque Country") (part "RES-2"))
    )
    (comp (ref "RCL2")
      (value "60")
      (footprint "RESC2013X60X35LL10T20")
      (description "SMD Chip Resistor, 10 kOhm, ± 1%, 125 mW, 0805 [2012 Metric], Thick Film, General Purpose")
      (fields (field (name "TOLERANCE") "1%") (field (name "Comment") "RC0805FR-0710KL"))
      (libsource (lib "EMEA- Formula Student Team Bizkaia- University of the Basque Country") (part "RES-2"))
    )
    (comp (ref "RV1")
      (value "VCAS080530C650DP")
      (footprint "VCAS080530C650DP-Footprint-1")
      (description "Varistor, 67V, 21Vac, 30Vdc, 0805")
      (fields (field (name "TOLERANCE") "10%"))
      (libsource (lib "EMEA- Formula Student Team Bizkaia- University of the Basque Country") (part "VCAS080530C650DP-Symbol-1"))
    )
    (comp (ref "TEMP1")
      (value "09455459011")
      (footprint "09455459011")
      (description "Harting Pushpull V4 Signal, 10Pins, Panel Side Insert For Angled Solder Termination")
      (libsource (lib "EMEA- Formula Student Team Bizkaia- University of the Basque Country") (part "09455459011-Symbol-1"))
    )
    (comp (ref "U1")
      (value "R-78K3.3-1.0")
      (footprint "BGA81C100P9X9_1100X1100X350")
      (description "R-78K-1.0 Series Single Output 3.3 V 1 A Non Isolated DC/DC Converter - SIP-3")
      (libsource (lib "EMEA- Formula Student Team Bizkaia- University of the Basque Country") (part "R-78K3.3-1.0-Symbol-1"))
    )
    (comp (ref "U2")
      (value "R-78C5.0-1.0")
      (footprint "R-78C5.0-1.0-Footprint-1")
      (description "1A DC/DC-Converter 'INNOLINE' SIP3 reg; V. In: 8-42; V. Out: 5.0; mA. Out: 1000")
      (libsource (lib "EMEA- Formula Student Team Bizkaia- University of the Basque Country") (part "R-78C5.0-1.0-Symbol-1"))
    )
    (comp (ref "U3")
      (value "R-78C5.0-1.0")
      (footprint "R-78C5.0-1.0-Footprint-1")
      (description "1A DC/DC-Converter 'INNOLINE' SIP3 reg; V. In: 8-42; V. Out: 5.0; mA. Out: 1000")
      (libsource (lib "EMEA- Formula Student Team Bizkaia- University of the Basque Country") (part "R-78C5.0-1.0-Symbol-1"))
    )
    (comp (ref "U4")
      (value "OPA990IDBVR")
      (footprint "FP-DBV0005A-IPC_B")
      (libsource (lib "EMEA- Formula Student Team Bizkaia- University of the Basque Country") (part "303ad2592cc7899f5e1082e1d8e7095"))
    )
    (comp (ref "U5")
      (value "OPA990IDBVR")
      (footprint "FP-DBV0005A-IPC_B")
      (libsource (lib "EMEA- Formula Student Team Bizkaia- University of the Basque Country") (part "303ad2592cc7899f5e1082e1d8e7095"))
    )
    (comp (ref "U6")
      (value "PIC24EP512GU810-I/PT")
      (footprint "TQFP-PT100_L")
      (libsource (lib "Altium Content Vault") (part "MC-16B-XXXGU810-TQ100"))
    )
    (comp (ref "U7")
      (value "OPA990IDBVR")
      (footprint "FP-DBV0005A-IPC_B")
      (libsource (lib "EMEA- Formula Student Team Bizkaia- University of the Basque Country") (part "303ad2592cc7899f5e1082e1d8e7095"))
    )
    (comp (ref "U8")
      (value "OPA990IDBVR")
      (footprint "FP-DBV0005A-IPC_B")
      (libsource (lib "EMEA- Formula Student Team Bizkaia- University of the Basque Country") (part "303ad2592cc7899f5e1082e1d8e7095"))
    )
    (comp (ref "U9")
      (value "OPA990IDBVR")
      (footprint "FP-DBV0005A-IPC_B")
      (libsource (lib "EMEA- Formula Student Team Bizkaia- University of the Basque Country") (part "303ad2592cc7899f5e1082e1d8e7095"))
    )
    (comp (ref "U10")
      (value "OPA990IDBVR")
      (footprint "FP-DBV0005A-IPC_B")
      (libsource (lib "EMEA- Formula Student Team Bizkaia- University of the Basque Country") (part "303ad2592cc7899f5e1082e1d8e7095"))
    )
    (comp (ref "U11")
      (value "OPA990IDBVR")
      (footprint "FP-DBV0005A-IPC_B")
      (libsource (lib "EMEA- Formula Student Team Bizkaia- University of the Basque Country") (part "303ad2592cc7899f5e1082e1d8e7095"))
    )
    (comp (ref "U12")
      (value "OPA990IDBVR")
      (footprint "FP-DBV0005A-IPC_B")
      (libsource (lib "EMEA- Formula Student Team Bizkaia- University of the Basque Country") (part "303ad2592cc7899f5e1082e1d8e7095"))
    )
    (comp (ref "UC1")
      (value "MCP2562FDT-E_SN")
      (footprint "SamacSys:SOIC127P600X175-8N")
      (description "Integrated Circuit")
      (fields
        (field (name "MANUFACTURER_PART_NUMBER") "MCP2562FDT-E/SN")
        (field (name "MOUSER PART NUMBER") "579-MCP2562FDT-E/SN")
      )
      (libsource (lib "*") (part "MCP2562FDT-E_SN"))
    )
    (comp (ref "UC2")
      (value "MCP2562FDT-E_SN")
      (footprint "SamacSys:SOIC127P600X175-8N")
      (description "Integrated Circuit")
      (fields
        (field (name "MANUFACTURER_PART_NUMBER") "MCP2562FDT-E/SN")
        (field (name "MOUSER PART NUMBER") "579-MCP2562FDT-E/SN")
      )
      (libsource (lib "*") (part "MCP2562FDT-E_SN"))
    )
    (comp (ref "Z1")
      (value "Zener 5")
      (footprint "ONSC-SOD-123-2-425-04_V")
      (description "Diode Zener Single 3.6V 5% 500mW Automotive 2-Pin SOD-123 T/R")
      (fields (field (name "TOLERANCE") "5%"))
      (libsource (lib "EMEA- Formula Student Team Bizkaia- University of the Basque Country") (part "ONSC-K1A2-2"))
    )
    (comp (ref "Z2")
      (value "Zener 3.6")
      (footprint "ONSC-SOD-123-2-425-04_V")
      (description "Diode Zener Single 3.6V 5% 500mW Automotive 2-Pin SOD-123 T/R")
      (fields (field (name "TOLERANCE") "5%"))
      (libsource (lib "EMEA- Formula Student Team Bizkaia- University of the Basque Country") (part "ONSC-K1A2-2"))
    )
    (comp (ref "Z3")
      (value "Zener 5")
      (footprint "ONSC-SOD-123-2-425-04_V")
      (description "Diode Zener Single 3.6V 5% 500mW Automotive 2-Pin SOD-123 T/R")
      (fields (field (name "TOLERANCE") "5%"))
      (libsource (lib "EMEA- Formula Student Team Bizkaia- University of the Basque Country") (part "ONSC-K1A2-2"))
    )
    (comp (ref "Z4")
      (value "Zener 3.3")
      (footprint "ONSC-SOD-123-2-425-04_V")
      (description "Diode Zener Single 3.6V 5% 500mW Automotive 2-Pin SOD-123 T/R")
      (fields (field (name "TOLERANCE") "5%"))
      (libsource (lib "EMEA- Formula Student Team Bizkaia- University of the Basque Country") (part "ONSC-K1A2-2"))
    )
    (comp (ref "Z5")
      (value "Zener 3.3")
      (footprint "ONSC-SOD-123-2-425-04_V")
      (description "Diode Zener Single 3.6V 5% 500mW Automotive 2-Pin SOD-123 T/R")
      (fields (field (name "TOLERANCE") "5%"))
      (libsource (lib "EMEA- Formula Student Team Bizkaia- University of the Basque Country") (part "ONSC-K1A2-2"))
    )
    (comp (ref "Z6")
      (value "Zener 3.3")
      (footprint "ONSC-SOD-123-2-425-04_V")
      (description "Diode Zener Single 3.6V 5% 500mW Automotive 2-Pin SOD-123 T/R")
      (fields (field (name "TOLERANCE") "5%"))
      (libsource (lib "EMEA- Formula Student Team Bizkaia- University of the Basque Country") (part "ONSC-K1A2-2"))
    )
    (comp (ref "Z7")
      (value "Zener 3.3")
      (footprint "ONSC-SOD-123-2-425-04_V")
      (description "Diode Zener Single 3.6V 5% 500mW Automotive 2-Pin SOD-123 T/R")
      (fields (field (name "TOLERANCE") "5%"))
      (libsource (lib "EMEA- Formula Student Team Bizkaia- University of the Basque Country") (part "ONSC-K1A2-2"))
    )
    (comp (ref "Z8")
      (value "Zener 3.3")
      (footprint "ONSC-SOD-123-2-425-04_V")
      (description "Diode Zener Single 3.6V 5% 500mW Automotive 2-Pin SOD-123 T/R")
      (fields (field (name "TOLERANCE") "5%"))
      (libsource (lib "EMEA- Formula Student Team Bizkaia- University of the Basque Country") (part "ONSC-K1A2-2"))
    )
    (comp (ref "Z9")
      (value "Zener 3.3")
      (footprint "ONSC-SOD-123-2-425-04_V")
      (description "Diode Zener Single 3.6V 5% 500mW Automotive 2-Pin SOD-123 T/R")
      (fields (field (name "TOLERANCE") "5%"))
      (libsource (lib "EMEA- Formula Student Team Bizkaia- University of the Basque Country") (part "ONSC-K1A2-2"))
    )
    (comp (ref "Z10")
      (value "Zener 3.3")
      (footprint "ONSC-SOD-123-2-425-04_V")
      (description "Diode Zener Single 3.6V 5% 500mW Automotive 2-Pin SOD-123 T/R")
      (fields (field (name "TOLERANCE") "5%"))
      (libsource (lib "EMEA- Formula Student Team Bizkaia- University of the Basque Country") (part "ONSC-K1A2-2"))
    )
  )
  (nets
    (net (code "1") (name "+5") (class "Default")
      (node (ref "C22") (pin "1") (pinfunction "1_1") (pintype "passive"))
      (node (ref "C23") (pin "1") (pinfunction "1_1") (pintype "passive"))
      (node (ref "C24") (pin "1") (pinfunction "1_1") (pintype "passive"))
      (node (ref "CC1") (pin "1") (pinfunction "1_1") (pintype "passive"))
      (node (ref "CC3") (pin "1") (pinfunction "1_1") (pintype "passive"))
      (node (ref "DASH1") (pin "3") (pinfunction "3_3") (pintype "passive"))
      (node (ref "DASH1") (pin "6") (pinfunction "6_6") (pintype "passive"))
      (node (ref "F2") (pin "2") (pinfunction "2_2") (pintype "passive"))
      (node (ref "ICSP1") (pin "5") (pintype "passive"))
      (node (ref "INT1") (pin "3") (pinfunction "3_3") (pintype "passive"))
      (node (ref "INT1") (pin "6") (pinfunction "6_6") (pintype "passive"))
      (node (ref "INT1") (pin "9") (pinfunction "9_9") (pintype "passive"))
      (node (ref "LTC1") (pin "1") (pinfunction "VCC_1") (pintype "passive"))
      (node (ref "LTC1") (pin "10") (pinfunction "REF_10") (pintype "passive"))
      (node (ref "LTC1") (pin "4") (pinfunction "IDLSEL_4") (pintype "passive"))
      (node (ref "LTC1") (pin "5") (pinfunction "IOVCC_5") (pintype "passive"))
      (node (ref "LTC1") (pin "7") (pinfunction "~{PD}_7") (pintype "passive"))
      (node (ref "U10") (pin "5") (pinfunction "V+_5") (pintype "power_in"))
      (node (ref "U11") (pin "5") (pinfunction "V+_5") (pintype "power_in"))
      (node (ref "U12") (pin "5") (pinfunction "V+_5") (pintype "power_in"))
      (node (ref "U4") (pin "5") (pinfunction "V+_5") (pintype "power_in"))
      (node (ref "U5") (pin "5") (pinfunction "V+_5") (pintype "power_in"))
      (node (ref "U7") (pin "5") (pinfunction "V+_5") (pintype "power_in"))
      (node (ref "U8") (pin "5") (pinfunction "V+_5") (pintype "power_in"))
      (node (ref "U9") (pin "5") (pinfunction "V+_5") (pintype "power_in"))
      (node (ref "UC1") (pin "3") (pinfunction "VDD_3") (pintype "passive"))
      (node (ref "UC2") (pin "3") (pinfunction "VDD_3") (pintype "passive"))
      (node (ref "Z1") (pin "1") (pinfunction "K_1") (pintype "passive"))
    )
    (net (code "2") (name "/1+") (class "Default")
      (node (ref "INA 2") (pin "2") (pinfunction "VIN-_2") (pintype "input"))
      (node (ref "R30") (pin "2") (pinfunction "2_2") (pintype "passive"))
      (node (ref "TEMP1") (pin "1") (pinfunction "1_1") (pintype "passive"))
    )
    (net (code "3") (name "/2+") (class "Default")
      (node (ref "INA 3") (pin "2") (pinfunction "VIN-_2") (pintype "input"))
      (node (ref "R32") (pin "2") (pinfunction "2_2") (pintype "passive"))
      (node (ref "TEMP1") (pin "3") (pinfunction "3_3") (pintype "passive"))
    )
    (net (code "4") (name "/3+") (class "Default")
      (node (ref "INA 4") (pin "2") (pinfunction "VIN-_2") (pintype "input"))
      (node (ref "R34") (pin "2") (pinfunction "2_2") (pintype "passive"))
      (node (ref "TEMP1") (pin "5") (pinfunction "5_5") (pintype "passive"))
    )
    (net (code "5") (name "/4+") (class "Default")
      (node (ref "INA 1") (pin "2") (pinfunction "VIN-_2") (pintype "input"))
      (node (ref "R36") (pin "2") (pinfunction "2_2") (pintype "passive"))
      (node (ref "TEMP1") (pin "7") (pinfunction "7_7") (pintype "passive"))
    )
    (net (code "6") (name "/AN_AUX1") (class "Default")
      (node (ref "R26") (pin "1") (pinfunction "1_1") (pintype "passive"))
      (node (ref "R27") (pin "1") (pinfunction "1_1") (pintype "passive"))
      (node (ref "U6") (pin "98") (pinfunction "AN26/PMD2/RP82/RE2_98") (pintype "bidirectional"))
      (node (ref "Z9") (pin "1") (pinfunction "K_1") (pintype "passive"))
    )
    (net (code "7") (name "/AN_AUX2") (class "Default")
      (node (ref "R17") (pin "1") (pinfunction "1_1") (pintype "passive"))
      (node (ref "R20") (pin "1") (pinfunction "1_1") (pintype "passive"))
      (node (ref "U6") (pin "99") (pinfunction "AN27/PMD3/RPI83/RE3_99") (pintype "bidirectional"))
      (node (ref "Z7") (pin "1") (pinfunction "K_1") (pintype "passive"))
    )
    (net (code "8") (name "/AUX") (class "Default")
      (node (ref "INT1") (pin "10") (pinfunction "10_10") (pintype "passive"))
      (node (ref "U6") (pin "33") (pinfunction "AN9/PMA7/RPI41/RB9_33") (pintype "bidirectional"))
    )
    (net (code "9") (name "/AUX1") (class "Default")
      (node (ref "DASH1") (pin "2") (pinfunction "2_2") (pintype "passive"))
      (node (ref "U12") (pin "3") (pinfunction "IN+_3") (pintype "tri_state"))
    )
    (net (code "10") (name "/AUX2") (class "Default")
      (node (ref "DASH1") (pin "5") (pinfunction "5_5") (pintype "passive"))
      (node (ref "U9") (pin "3") (pinfunction "IN+_3") (pintype "tri_state"))
    )
    (net (code "11") (name "/CANH_0") (class "Default")
      (node (ref "2") (pin "1") (pinfunction "cathode_1_1") (pintype "passive"))
      (node (ref "CAN2") (pin "2") (pinfunction "2_2") (pintype "passive"))
      (node (ref "CHB3") (pin "1") (pinfunction "1_1") (pintype "passive"))
      (node (ref "DASH1") (pin "9") (pinfunction "9_9") (pintype "passive"))
      (node (ref "L4") (pin "4") (pinfunction "4_4") (pintype "passive"))
      (node (ref "RCH2") (pin "2") (pinfunction "2_2") (pintype "passive"))
      (node (ref "TEMP1") (pin "9") (pinfunction "9_9") (pintype "passive"))
    )
    (net (code "12") (name "/CANH_3") (class "Default")
      (node (ref "1") (pin "1") (pinfunction "cathode_1_1") (pintype "passive"))
      (node (ref "CAN1") (pin "2") (pinfunction "2_2") (pintype "passive"))
      (node (ref "CHB2") (pin "1") (pinfunction "1_1") (pintype "passive"))
      (node (ref "L1") (pin "4") (pinfunction "4_4") (pintype "passive"))
      (node (ref "OUT1") (pin "8") (pinfunction "8_8") (pintype "passive"))
      (node (ref "RCH1") (pin "2") (pinfunction "2_2") (pintype "passive"))
    )
    (net (code "13") (name "/CANL_0") (class "Default")
      (node (ref "2") (pin "2") (pinfunction "cathode_2_2") (pintype "passive"))
      (node (ref "CAN2") (pin "1") (pinfunction "1_1") (pintype "passive"))
      (node (ref "CLB3") (pin "1") (pinfunction "1_1") (pintype "passive"))
      (node (ref "DASH1") (pin "10") (pinfunction "10_10") (pintype "passive"))
      (node (ref "L4") (pin "1") (pinfunction "1_1") (pintype "passive"))
      (node (ref "RCL2") (pin "2") (pinfunction "2_2") (pintype "passive"))
      (node (ref "TEMP1") (pin "10") (pinfunction "10_10") (pintype "passive"))
    )
    (net (code "14") (name "/CANL_3") (class "Default")
      (node (ref "1") (pin "2") (pinfunction "cathode_2_2") (pintype "passive"))
      (node (ref "CAN1") (pin "1") (pinfunction "1_1") (pintype "passive"))
      (node (ref "CLB2") (pin "1") (pinfunction "1_1") (pintype "passive"))
      (node (ref "L1") (pin "1") (pinfunction "1_1") (pintype "passive"))
      (node (ref "OUT1") (pin "9") (pinfunction "9_9") (pintype "passive"))
      (node (ref "RCL1") (pin "2") (pinfunction "2_2") (pintype "passive"))
    )
    (net (code "15") (name "/CAUDAL_A") (class "Default")
      (node (ref "LTC1") (pin "2") (pinfunction "VOUTA_2") (pintype "passive"))
      (node (ref "U8") (pin "3") (pinfunction "IN+_3") (pintype "tri_state"))
    )
    (net (code "16") (name "/CAUDAL_P") (class "Default")
      (node (ref "INT1") (pin "8") (pinfunction "8_8") (pintype "passive"))
      (node (ref "LTC1") (pin "9") (pinfunction "INA_9") (pintype "passive"))
    )
    (net (code "17") (name "/CAUDAL_reg") (class "Default")
      (node (ref "R14") (pin "1") (pinfunction "1_1") (pintype "passive"))
      (node (ref "R15") (pin "1") (pinfunction "1_1") (pintype "passive"))
      (node (ref "U6") (pin "100") (pinfunction "AN28/PMD4/RP84/RE4_100") (pintype "bidirectional"))
      (node (ref "Z6") (pin "1") (pinfunction "K_1") (pintype "passive"))
    )
    (net (code "18") (name "/DIRECCION") (class "Default")
      (node (ref "OUT1") (pin "5") (pinfunction "5_5") (pintype "passive"))
      (node (ref "R24") (pin "1") (pinfunction "1_1") (pintype "passive"))
      (node (ref "Z10") (pin "1") (pinfunction "K_1") (pintype "passive"))
    )
    (net (code "19") (name "/LED_0") (class "Default")
      (node (ref "D2") (pin "1") (pinfunction "A_1") (pintype "passive"))
      (node (ref "U6") (pin "18") (pinfunction "AN20/RPI88/RE8_18") (pintype "bidirectional"))
    )
    (net (code "20") (name "/LED_1") (class "Default")
      (node (ref "D1") (pin "1") (pinfunction "A_1") (pintype "passive"))
      (node (ref "U6") (pin "5") (pinfunction "AN31/PMD7/RP87/RE7_5") (pintype "bidirectional"))
    )
    (net (code "21") (name "/MCLR") (class "Default")
      (node (ref "ICSP1") (pin "6") (pintype "passive"))
      (node (ref "R28") (pin "2") (pinfunction "2_2") (pintype "passive"))
      (node (ref "U6") (pin "13") (pinfunction "~{MCLR}_13") (pintype "input"))
    )
    (net (code "22") (name "/OSC1") (class "Default")
      (node (ref "C19") (pin "1") (pinfunction "1_1") (pintype "passive"))
      (node (ref "OSC 1") (pin "2") (pinfunction "2_2") (pintype "passive"))
      (node (ref "R25") (pin "2") (pinfunction "2_2") (pintype "passive"))
      (node (ref "U6") (pin "63") (pinfunction "OSC1/RPI60/RC12_63") (pintype "bidirectional"))
    )
    (net (code "23") (name "/OSC2") (class "Default")
      (node (ref "C18") (pin "1") (pinfunction "1_1") (pintype "passive"))
      (node (ref "OSC 1") (pin "1") (pinfunction "1_1") (pintype "passive"))
      (node (ref "R25") (pin "1") (pinfunction "1_1") (pintype "passive"))
      (node (ref "U6") (pin "64") (pinfunction "OSC2/CLKO/RC15_64") (pintype "bidirectional"))
    )
    (net (code "24") (name "/PGC") (class "Default")
      (node (ref "ICSP1") (pin "2") (pintype "passive"))
      (node (ref "U6") (pin "26") (pinfunction "PGEC1/AN6/RPI38/RB6_26") (pintype "bidirectional"))
    )
    (net (code "25") (name "/PGD") (class "Default")
      (node (ref "ICSP1") (pin "3") (pintype "passive"))
      (node (ref "U6") (pin "27") (pinfunction "PGED1/AN7/RCV/RPI39/RB7_27") (pintype "bidirectional"))
    )
    (net (code "26") (name "/PGM") (class "Default")
      (node (ref "D3") (pin "1") (pinfunction "A_1") (pintype "passive"))
      (node (ref "ICSP1") (pin "1") (pintype "passive"))
    )
    (net (code "27") (name "/RX_CAN") (class "Default")
      (node (ref "U6") (pin "80") (pinfunction "RPI77/RD13_80") (pintype "bidirectional"))
      (node (ref "UC2") (pin "4") (pinfunction "RXD_4") (pintype "passive"))
    )
    (net (code "28") (name "/RX_CAN3") (class "Default")
      (node (ref "U6") (pin "91") (pinfunction "AN22/RPI22/RA6_91") (pintype "bidirectional"))
      (node (ref "UC1") (pin "4") (pinfunction "RXD_4") (pintype "passive"))
    )
    (net (code "29") (name "/SD_amp") (class "Default")
      (node (ref "R11") (pin "1") (pinfunction "1_1") (pintype "passive"))
      (node (ref "R8") (pin "1") (pinfunction "1_1") (pintype "passive"))
      (node (ref "U6") (pin "3") (pinfunction "AN29/PMD5/RP85/RE5_3") (pintype "bidirectional"))
      (node (ref "Z5") (pin "1") (pinfunction "K_1") (pintype "passive"))
    )
    (net (code "30") (name "/SD_ruido") (class "Default")
      (node (ref "INT1") (pin "2") (pinfunction "2_2") (pintype "passive"))
      (node (ref "R12") (pin "1") (pinfunction "1_1") (pintype "passive"))
    )
    (net (code "31") (name "/SI_amp") (class "Default")
      (node (ref "R18") (pin "1") (pinfunction "1_1") (pintype "passive"))
      (node (ref "R21") (pin "1") (pinfunction "1_1") (pintype "passive"))
      (node (ref "U6") (pin "4") (pinfunction "AN30/PMD6/RPI86/RE6_4") (pintype "bidirectional"))
      (node (ref "Z8") (pin "1") (pinfunction "K_1") (pintype "passive"))
    )
    (net (code "32") (name "/SI_ruido") (class "Default")
      (node (ref "INT1") (pin "5") (pinfunction "5_5") (pintype "passive"))
      (node (ref "R22") (pin "1") (pinfunction "1_1") (pintype "passive"))
    )
    (net (code "33") (name "/T1") (class "Default")
      (node (ref "INA 2") (pin "6") (pinfunction "VOUT_6") (pintype "output"))
      (node (ref "U6") (pin "44") (pinfunction "AN15/PMA0/RPI47/RB15_44") (pintype "bidirectional"))
    )
    (net (code "34") (name "/T2") (class "Default")
      (node (ref "INA 3") (pin "6") (pinfunction "VOUT_6") (pintype "output"))
      (node (ref "U6") (pin "34") (pinfunction "AN10/CVREF/PMA13/RPI42/RB10_34") (pintype "bidirectional"))
    )
    (net (code "35") (name "/T3") (class "Default")
      (node (ref "INA 4") (pin "6") (pinfunction "VOUT_6") (pintype "output"))
      (node (ref "U6") (pin "43") (pinfunction "AN14/PMA1/RPI46/RB14_43") (pintype "bidirectional"))
    )
    (net (code "36") (name "/T4") (class "Default")
      (node (ref "INA 1") (pin "6") (pinfunction "VOUT_6") (pintype "output"))
      (node (ref "U6") (pin "35") (pinfunction "AN11/PMA12/RPI43/RB11_35") (pintype "bidirectional"))
    )
    (net (code "37") (name "/TX_CAN") (class "Default")
      (node (ref "U6") (pin "81") (pinfunction "PMWR/RP68/RD4_81") (pintype "bidirectional"))
      (node (ref "UC2") (pin "1") (pinfunction "TXD_1") (pintype "passive"))
    )
    (net (code "38") (name "/TX_CAN3") (class "Default")
      (node (ref "U6") (pin "90") (pinfunction "RP112/RG0_90") (pintype "bidirectional"))
      (node (ref "UC1") (pin "1") (pinfunction "TXD_1") (pintype "passive"))
    )
    (net (code "39") (name "/V1") (class "Default")
      (node (ref "INA 2") (pin "3") (pinfunction "VIN+_3") (pintype "input"))
      (node (ref "R29") (pin "1") (pinfunction "1_1") (pintype "passive"))
      (node (ref "R37") (pin "1") (pinfunction "CCW_1") (pintype "passive"))
    )
    (net (code "40") (name "/V2") (class "Default")
      (node (ref "INA 3") (pin "3") (pinfunction "VIN+_3") (pintype "input"))
      (node (ref "R31") (pin "1") (pinfunction "1_1") (pintype "passive"))
      (node (ref "R38") (pin "1") (pinfunction "CCW_1") (pintype "passive"))
    )
    (net (code "41") (name "/V3") (class "Default")
      (node (ref "INA 4") (pin "3") (pinfunction "VIN+_3") (pintype "input"))
      (node (ref "R33") (pin "1") (pinfunction "1_1") (pintype "passive"))
      (node (ref "R39") (pin "1") (pinfunction "CCW_1") (pintype "passive"))
    )
    (net (code "42") (name "/V4") (class "Default")
      (node (ref "INA 1") (pin "3") (pinfunction "VIN+_3") (pintype "input"))
      (node (ref "R35") (pin "1") (pinfunction "1_1") (pintype "passive"))
      (node (ref "R40") (pin "1") (pinfunction "CCW_1") (pintype "passive"))
    )
    (net (code "43") (name "/VCAP") (class "Default")
      (node (ref "CAP1") (pin "2") (pinfunction "A_2") (pintype "passive"))
      (node (ref "U6") (pin "85") (pinfunction "VCAP_85") (pintype "passive"))
    )
    (net (code "44") (name "/ZRACK") (class "Default")
      (node (ref "OUT1") (pin "2") (pinfunction "2_2") (pintype "passive"))
      (node (ref "U4") (pin "3") (pinfunction "IN+_3") (pintype "tri_state"))
    )
    (net (code "45") (name "/ZRACK-Reg") (class "Default")
      (node (ref "R7") (pin "1") (pinfunction "1_1") (pintype "passive"))
      (node (ref "R9") (pin "1") (pinfunction "1_1") (pintype "passive"))
      (node (ref "U6") (pin "94") (pinfunction "AN25/PMD1/RPI81/RE1_94") (pintype "bidirectional"))
      (node (ref "Z4") (pin "1") (pinfunction "K_1") (pintype "passive"))
    )
    (net (code "46") (name "3.3V") (class "Default")
      (node (ref "C11") (pin "1") (pinfunction "1_1") (pintype "passive"))
      (node (ref "C12") (pin "1") (pinfunction "1_1") (pintype "passive"))
      (node (ref "C14") (pin "1") (pinfunction "1_1") (pintype "passive"))
      (node (ref "C15") (pin "1") (pinfunction "1_1") (pintype "passive"))
      (node (ref "C20") (pin "2") (pinfunction "2_2") (pintype "passive"))
      (node (ref "C21") (pin "2") (pinfunction "2_2") (pintype "passive"))
      (node (ref "C25") (pin "2") (pinfunction "2_2") (pintype "passive"))
      (node (ref "C26") (pin "2") (pinfunction "2_2") (pintype "passive"))
      (node (ref "CC2") (pin "2") (pinfunction "2_2") (pintype "passive"))
      (node (ref "CC4") (pin "2") (pinfunction "2_2") (pintype "passive"))
      (node (ref "F1") (pin "2") (pinfunction "2_2") (pintype "passive"))
      (node (ref "INA 1") (pin "7") (pinfunction "V+_7") (pintype "power_in"))
      (node (ref "INA 2") (pin "7") (pinfunction "V+_7") (pintype "power_in"))
      (node (ref "INA 3") (pin "7") (pinfunction "V+_7") (pintype "power_in"))
      (node (ref "INA 4") (pin "7") (pinfunction "V+_7") (pintype "power_in"))
      (node (ref "OUT1") (pin "3") (pinfunction "3_3") (pintype "passive"))
      (node (ref "OUT1") (pin "6") (pinfunction "6_6") (pintype "passive"))
      (node (ref "R28") (pin "1") (pinfunction "1_1") (pintype "passive"))
      (node (ref "R29") (pin "2") (pinfunction "2_2") (pintype "passive"))
      (node (ref "R30") (pin "1") (pinfunction "1_1") (pintype "passive"))
      (node (ref "R31") (pin "2") (pinfunction "2_2") (pintype "passive"))
      (node (ref "R32") (pin "1") (pinfunction "1_1") (pintype "passive"))
      (node (ref "R33") (pin "2") (pinfunction "2_2") (pintype "passive"))
      (node (ref "R34") (pin "1") (pinfunction "1_1") (pintype "passive"))
      (node (ref "R35") (pin "2") (pinfunction "2_2") (pintype "passive"))
      (node (ref "R36") (pin "1") (pinfunction "1_1") (pintype "passive"))
      (node (ref "U6") (pin "16") (pinfunction "VDD_16") (pintype "power_in"))
      (node (ref "U6") (pin "2") (pinfunction "VDD_2") (pintype "power_in"))
      (node (ref "U6") (pin "30") (pinfunction "AVDD_30") (pintype "power_in"))
      (node (ref "U6") (pin "37") (pinfunction "VDD_37") (pintype "power_in"))
      (node (ref "U6") (pin "46") (pinfunction "VDD_46") (pintype "power_in"))
      (node (ref "U6") (pin "62") (pinfunction "VDD_62") (pintype "power_in"))
      (node (ref "U6") (pin "86") (pinfunction "VDD_86") (pintype "power_in"))
      (node (ref "UC1") (pin "5") (pinfunction "VIO_5") (pintype "passive"))
      (node (ref "UC2") (pin "5") (pinfunction "VIO_5") (pintype "passive"))
      (node (ref "Z2") (pin "1") (pinfunction "K_1") (pintype "passive"))
    )
    (net (code "47") (name "12V") (class "Default")
      (node (ref "F3") (pin "2") (pinfunction "2_2") (pintype "passive"))
      (node (ref "OUT1") (pin "10") (pinfunction "10_10") (pintype "passive"))
      (node (ref "Z3") (pin "1") (pinfunction "K_1") (pintype "passive"))
    )
    (net (code "48") (name "24V") (class "Default")
      (node (ref "C3") (pin "1") (pinfunction "1_1") (pintype "passive"))
      (node (ref "C6") (pin "1") (pinfunction "1_1") (pintype "passive"))
      (node (ref "C9") (pin "1") (pinfunction "1_1") (pintype "passive"))
      (node (ref "F4") (pin "1") (pinfunction "1_1") (pintype "passive"))
      (node (ref "L2") (pin "1") (pinfunction "1_1") (pintype "passive"))
      (node (ref "L3") (pin "1") (pinfunction "1_1") (pintype "passive"))
      (node (ref "L5") (pin "1") (pinfunction "1_1") (pintype "passive"))
      (node (ref "RV1") (pin "1") (pinfunction "1_1") (pintype "passive"))
    )
    (net (code "49") (name "GND") (class "Default")
      (node (ref "1") (pin "3") (pinfunction "common_cathode_3") (pintype "passive"))
      (node (ref "2") (pin "3") (pinfunction "common_cathode_3") (pintype "passive"))
      (node (ref "C1") (pin "2") (pinfunction "2_2") (pintype "passive"))
      (node (ref "C11") (pin "2") (pinfunction "2_2") (pintype "passive"))
      (node (ref "C12") (pin "2") (pinfunction "2_2") (pintype "passive"))
      (node (ref "C13") (pin "2") (pinfunction "2_2") (pintype "passive"))
      (node (ref "C14") (pin "2") (pinfunction "2_2") (pintype "passive"))
      (node (ref "C15") (pin "2") (pinfunction "2_2") (pintype "passive"))
      (node (ref "C17") (pin "2") (pinfunction "2_2") (pintype "passive"))
      (node (ref "C18") (pin "2") (pinfunction "2_2") (pintype "passive"))
      (node (ref "C19") (pin "2") (pinfunction "2_2") (pintype "passive"))
      (node (ref "C2") (pin "2") (pinfunction "2_2") (pintype "passive"))
      (node (ref "C20") (pin "1") (pinfunction "1_1") (pintype "passive"))
      (node (ref "C21") (pin "1") (pinfunction "1_1") (pintype "passive"))
      (node (ref "C22") (pin "2") (pinfunction "2_2") (pintype "passive"))
      (node (ref "C23") (pin "2") (pinfunction "2_2") (pintype "passive"))
      (node (ref "C24") (pin "2") (pinfunction "2_2") (pintype "passive"))
      (node (ref "C25") (pin "1") (pinfunction "1_1") (pintype "passive"))
      (node (ref "C26") (pin "1") (pinfunction "1_1") (pintype "passive"))
      (node (ref "C3") (pin "2") (pinfunction "2_2") (pintype "passive"))
      (node (ref "C4") (pin "2") (pinfunction "2_2") (pintype "passive"))
      (node (ref "C5") (pin "2") (pinfunction "2_2") (pintype "passive"))
      (node (ref "C6") (pin "2") (pinfunction "2_2") (pintype "passive"))
      (node (ref "C7") (pin "2") (pinfunction "2_2") (pintype "passive"))
      (node (ref "C8") (pin "2") (pinfunction "2_2") (pintype "passive"))
      (node (ref "C9") (pin "2") (pinfunction "2_2") (pintype "passive"))
      (node (ref "CAP1") (pin "1") (pinfunction "C_1") (pintype "passive"))
      (node (ref "CB1") (pin "2") (pinfunction "2_2") (pintype "passive"))
      (node (ref "CB2") (pin "2") (pinfunction "2_2") (pintype "passive"))
      (node (ref "CC1") (pin "2") (pinfunction "2_2") (pintype "passive"))
      (node (ref "CC2") (pin "1") (pinfunction "1_1") (pintype "passive"))
      (node (ref "CC3") (pin "2") (pinfunction "2_2") (pintype "passive"))
      (node (ref "CC4") (pin "1") (pinfunction "1_1") (pintype "passive"))
      (node (ref "CHB1") (pin "2") (pinfunction "2_2") (pintype "passive"))
      (node (ref "CHB2") (pin "2") (pinfunction "2_2") (pintype "passive"))
      (node (ref "CHB3") (pin "2") (pinfunction "2_2") (pintype "passive"))
      (node (ref "CHB4") (pin "2") (pinfunction "2_2") (pintype "passive"))
      (node (ref "CLB1") (pin "2") (pinfunction "2_2") (pintype "passive"))
      (node (ref "CLB2") (pin "2") (pinfunction "2_2") (pintype "passive"))
      (node (ref "CLB3") (pin "2") (pinfunction "2_2") (pintype "passive"))
      (node (ref "CLB4") (pin "2") (pinfunction "2_2") (pintype "passive"))
      (node (ref "DASH1") (pin "1") (pinfunction "1_1") (pintype "passive"))
      (node (ref "DASH1") (pin "4") (pinfunction "4_4") (pintype "passive"))
      (node (ref "DASH1") (pin "7") (pinfunction "7_7") (pintype "passive"))
      (node (ref "DASH1") (pin "MH1") (pinfunction "MH1_MH1") (pintype "passive"))
      (node (ref "DASH1") (pin "MH2") (pinfunction "MH2_MH2") (pintype "passive"))
      (node (ref "DASH1") (pin "MH5") (pinfunction "MH5_MH5") (pintype "passive"))
      (node (ref "DASH1") (pin "MH6") (pinfunction "MH6_MH6") (pintype "passive"))
      (node (ref "DR1") (pin "1") (pinfunction "A_1") (pintype "passive"))
      (node (ref "ICSP1") (pin "4") (pintype "passive"))
      (node (ref "INA 1") (pin "4") (pinfunction "V-_4") (pintype "power_in"))
      (node (ref "INA 1") (pin "5") (pinfunction "REF_5") (pintype "input"))
      (node (ref "INA 2") (pin "4") (pinfunction "V-_4") (pintype "power_in"))
      (node (ref "INA 2") (pin "5") (pinfunction "REF_5") (pintype "input"))
      (node (ref "INA 3") (pin "4") (pinfunction "V-_4") (pintype "power_in"))
      (node (ref "INA 3") (pin "5") (pinfunction "REF_5") (pintype "input"))
      (node (ref "INA 4") (pin "4") (pinfunction "V-_4") (pintype "power_in"))
      (node (ref "INA 4") (pin "5") (pinfunction "REF_5") (pintype "input"))
      (node (ref "INT1") (pin "1") (pinfunction "1_1") (pintype "passive"))
      (node (ref "INT1") (pin "4") (pinfunction "4_4") (pintype "passive"))
      (node (ref "INT1") (pin "7") (pinfunction "7_7") (pintype "passive"))
      (node (ref "INT1") (pin "MH1") (pinfunction "MH1_MH1") (pintype "passive"))
      (node (ref "INT1") (pin "MH2") (pinfunction "MH2_MH2") (pintype "passive"))
      (node (ref "INT1") (pin "MH5") (pinfunction "MH5_MH5") (pintype "passive"))
      (node (ref "INT1") (pin "MH6") (pinfunction "MH6_MH6") (pintype "passive"))
      (node (ref "LTC1") (pin "11") (pinfunction "REFSEL_11") (pintype "passive"))
      (node (ref "LTC1") (pin "12") (pinfunction "GND_2_12") (pintype "passive"))
      (node (ref "LTC1") (pin "6") (pinfunction "GND_1_6") (pintype "passive"))
      (node (ref "OUT1") (pin "1") (pinfunction "1_1") (pintype "passive"))
      (node (ref "OUT1") (pin "4") (pinfunction "4_4") (pintype "passive"))
      (node (ref "OUT1") (pin "7") (pinfunction "7_7") (pintype "passive"))
      (node (ref "OUT1") (pin "MH1") (pinfunction "MH1_MH1") (pintype "passive"))
      (node (ref "OUT1") (pin "MH2") (pinfunction "MH2_MH2") (pintype "passive"))
      (node (ref "OUT1") (pin "MH5") (pinfunction "MH5_MH5") (pintype "passive"))
      (node (ref "OUT1") (pin "MH6") (pinfunction "MH6_MH6") (pintype "passive"))
      (node (ref "R1") (pin "2") (pinfunction "2_2") (pintype "passive"))
      (node (ref "R10") (pin "2") (pinfunction "2_2") (pintype "passive"))
      (node (ref "R11") (pin "2") (pinfunction "2_2") (pintype "passive"))
      (node (ref "R15") (pin "2") (pinfunction "2_2") (pintype "passive"))
      (node (ref "R19") (pin "2") (pinfunction "2_2") (pintype "passive"))
      (node (ref "R2") (pin "2") (pinfunction "2_2") (pintype "passive"))
      (node (ref "R20") (pin "2") (pinfunction "2_2") (pintype "passive"))
      (node (ref "R21") (pin "2") (pinfunction "2_2") (pintype "passive"))
      (node (ref "R27") (pin "2") (pinfunction "2_2") (pintype "passive"))
      (node (ref "R3") (pin "1") (pinfunction "1_1") (pintype "passive"))
      (node (ref "R37") (pin "2") (pinfunction "WIPER_2") (pintype "passive"))
      (node (ref "R38") (pin "2") (pinfunction "WIPER_2") (pintype "passive"))
      (node (ref "R39") (pin "2") (pinfunction "WIPER_2") (pintype "passive"))
      (node (ref "R4") (pin "1") (pinfunction "1_1") (pintype "passive"))
      (node (ref "R40") (pin "2") (pinfunction "WIPER_2") (pintype "passive"))
      (node (ref "R5") (pin "1") (pinfunction "1_1") (pintype "passive"))
      (node (ref "R9") (pin "2") (pinfunction "2_2") (pintype "passive"))
      (node (ref "RV1") (pin "2") (pinfunction "2_2") (pintype "passive"))
      (node (ref "TEMP1") (pin "2") (pinfunction "2_2") (pintype "passive"))
      (node (ref "TEMP1") (pin "4") (pinfunction "4_4") (pintype "passive"))
      (node (ref "TEMP1") (pin "6") (pinfunction "6_6") (pintype "passive"))
      (node (ref "TEMP1") (pin "8") (pinfunction "8_8") (pintype "passive"))
      (node (ref "TEMP1") (pin "MH1") (pinfunction "MH1_MH1") (pintype "passive"))
      (node (ref "TEMP1") (pin "MH2") (pinfunction "MH2_MH2") (pintype "passive"))
      (node (ref "TEMP1") (pin "MH5") (pinfunction "MH5_MH5") (pintype "passive"))
      (node (ref "TEMP1") (pin "MH6") (pinfunction "MH6_MH6") (pintype "passive"))
      (node (ref "U1") (pin "2") (pinfunction "GND_2") (pintype "passive"))
      (node (ref "U10") (pin "2") (pinfunction "V-_2") (pintype "power_in"))
      (node (ref "U11") (pin "2") (pinfunction "V-_2") (pintype "power_in"))
      (node (ref "U12") (pin "2") (pinfunction "V-_2") (pintype "power_in"))
      (node (ref "U2") (pin "2") (pinfunction "GND_2") (pintype "passive"))
      (node (ref "U3") (pin "2") (pinfunction "GND_2") (pintype "passive"))
      (node (ref "U4") (pin "2") (pinfunction "V-_2") (pintype "power_in"))
      (node (ref "U5") (pin "2") (pinfunction "V-_2") (pintype "power_in"))
      (node (ref "U6") (pin "15") (pinfunction "VSS_15") (pintype "power_in"))
      (node (ref "U6") (pin "31") (pinfunction "AVSS_31") (pintype "power_in"))
      (node (ref "U6") (pin "36") (pinfunction "VSS_36") (pintype "power_in"))
      (node (ref "U6") (pin "45") (pinfunction "VSS_45") (pintype "power_in"))
      (node (ref "U6") (pin "65") (pinfunction "VSS_65") (pintype "power_in"))
      (node (ref "U6") (pin "75") (pinfunction "VSS_75") (pintype "power_in"))
      (node (ref "U7") (pin "2") (pinfunction "V-_2") (pintype "power_in"))
      (node (ref "U8") (pin "2") (pinfunction "V-_2") (pintype "power_in"))
      (node (ref "U9") (pin "2") (pinfunction "V-_2") (pintype "power_in"))
      (node (ref "UC1") (pin "2") (pinfunction "VSS_2") (pintype "passive"))
      (node (ref "UC2") (pin "2") (pinfunction "VSS_2") (pintype "passive"))
      (node (ref "Z1") (pin "2") (pinfunction "A_2") (pintype "passive"))
      (node (ref "Z10") (pin "2") (pinfunction "A_2") (pintype "passive"))
      (node (ref "Z2") (pin "2") (pinfunction "A_2") (pintype "passive"))
      (node (ref "Z3") (pin "2") (pinfunction "A_2") (pintype "passive"))
      (node (ref "Z4") (pin "2") (pinfunction "A_2") (pintype "passive"))
      (node (ref "Z5") (pin "2") (pinfunction "A_2") (pintype "passive"))
      (node (ref "Z6") (pin "2") (pinfunction "A_2") (pintype "passive"))
      (node (ref "Z7") (pin "2") (pinfunction "A_2") (pintype "passive"))
      (node (ref "Z8") (pin "2") (pinfunction "A_2") (pintype "passive"))
      (node (ref "Z9") (pin "2") (pinfunction "A_2") (pintype "passive"))
    )
    (net (code "50") (name "Net-(C13-Pad1)") (class "Default")
      (node (ref "C13") (pin "1") (pinfunction "1_1") (pintype "passive"))
      (node (ref "R12") (pin "2") (pinfunction "2_2") (pintype "passive"))
      (node (ref "R13") (pin "1") (pinfunction "1_1") (pintype "passive"))
      (node (ref "R6") (pin "1") (pinfunction "1_1") (pintype "passive"))
    )
    (net (code "51") (name "Net-(C17-Pad1)") (class "Default")
      (node (ref "C17") (pin "1") (pinfunction "1_1") (pintype "passive"))
      (node (ref "R16") (pin "1") (pinfunction "1_1") (pintype "passive"))
      (node (ref "R22") (pin "2") (pinfunction "2_2") (pintype "passive"))
      (node (ref "R23") (pin "1") (pinfunction "1_1") (pintype "passive"))
    )
    (net (code "52") (name "Net-(CB1-Pad1)") (class "Default")
      (node (ref "CB1") (pin "1") (pinfunction "1_1") (pintype "passive"))
      (node (ref "RCH1") (pin "1") (pinfunction "1_1") (pintype "passive"))
      (node (ref "RCL1") (pin "1") (pinfunction "1_1") (pintype "passive"))
    )
    (net (code "53") (name "Net-(CB2-Pad1)") (class "Default")
      (node (ref "CB2") (pin "1") (pinfunction "1_1") (pintype "passive"))
      (node (ref "RCH2") (pin "1") (pinfunction "1_1") (pintype "passive"))
      (node (ref "RCL2") (pin "1") (pinfunction "1_1") (pintype "passive"))
    )
    (net (code "54") (name "Net-(D1-K)") (class "Default")
      (node (ref "D1") (pin "2") (pinfunction "K_2") (pintype "passive"))
      (node (ref "R3") (pin "2") (pinfunction "2_2") (pintype "passive"))
    )
    (net (code "55") (name "Net-(D2-K)") (class "Default")
      (node (ref "D2") (pin "2") (pinfunction "K_2") (pintype "passive"))
      (node (ref "R4") (pin "2") (pinfunction "2_2") (pintype "passive"))
    )
    (net (code "56") (name "Net-(D3-K)") (class "Default")
      (node (ref "D3") (pin "2") (pinfunction "K_2") (pintype "passive"))
      (node (ref "R5") (pin "2") (pinfunction "2_2") (pintype "passive"))
    )
    (net (code "57") (name "Net-(DR1-K)") (class "Default")
      (node (ref "DASH1") (pin "8") (pinfunction "8_8") (pintype "passive"))
      (node (ref "DR1") (pin "2") (pinfunction "K_2") (pintype "passive"))
      (node (ref "F4") (pin "2") (pinfunction "2_2") (pintype "passive"))
    )
    (net (code "58") (name "Net-(INA 1-RG1)") (class "Default")
      (node (ref "INA 1") (pin "1") (pinfunction "RG1_1") (pintype "bidirectional"))
      (node (ref "R41") (pin "2") (pinfunction "2_2") (pintype "passive"))
    )
    (net (code "59") (name "Net-(INA 1-RG2)") (class "Default")
      (node (ref "INA 1") (pin "8") (pinfunction "RG2_8") (pintype "bidirectional"))
      (node (ref "R41") (pin "1") (pinfunction "1_1") (pintype "passive"))
    )
    (net (code "60") (name "Net-(INA 2-RG1)") (class "Default")
      (node (ref "INA 2") (pin "1") (pinfunction "RG1_1") (pintype "bidirectional"))
      (node (ref "R42") (pin "2") (pinfunction "2_2") (pintype "passive"))
    )
    (net (code "61") (name "Net-(INA 2-RG2)") (class "Default")
      (node (ref "INA 2") (pin "8") (pinfunction "RG2_8") (pintype "bidirectional"))
      (node (ref "R42") (pin "1") (pinfunction "1_1") (pintype "passive"))
    )
    (net (code "62") (name "Net-(INA 3-RG1)") (class "Default")
      (node (ref "INA 3") (pin "1") (pinfunction "RG1_1") (pintype "bidirectional"))
      (node (ref "R43") (pin "2") (pinfunction "2_2") (pintype "passive"))
    )
    (net (code "63") (name "Net-(INA 3-RG2)") (class "Default")
      (node (ref "INA 3") (pin "8") (pinfunction "RG2_8") (pintype "bidirectional"))
      (node (ref "R43") (pin "1") (pinfunction "1_1") (pintype "passive"))
    )
    (net (code "64") (name "Net-(INA 4-RG1)") (class "Default")
      (node (ref "INA 4") (pin "1") (pinfunction "RG1_1") (pintype "bidirectional"))
      (node (ref "R44") (pin "2") (pinfunction "2_2") (pintype "passive"))
    )
    (net (code "65") (name "Net-(INA 4-RG2)") (class "Default")
      (node (ref "INA 4") (pin "8") (pinfunction "RG2_8") (pintype "bidirectional"))
      (node (ref "R44") (pin "1") (pinfunction "1_1") (pintype "passive"))
    )
    (net (code "66") (name "Net-(U1-+VIN)") (class "Default")
      (node (ref "C4") (pin "1") (pinfunction "1_1") (pintype "passive"))
      (node (ref "L2") (pin "2") (pinfunction "2_2") (pintype "passive"))
      (node (ref "U1") (pin "1") (pinfunction "+VIN_1") (pintype "passive"))
    )
    (net (code "67") (name "Net-(U1-+VOUT)") (class "Default")
      (node (ref "C5") (pin "1") (pinfunction "1_1") (pintype "passive"))
      (node (ref "F1") (pin "1") (pinfunction "1_1") (pintype "passive"))
      (node (ref "U1") (pin "3") (pinfunction "+VOUT_3") (pintype "passive"))
    )
    (net (code "68") (name "Net-(U2-+VIN)") (class "Default")
      (node (ref "C1") (pin "1") (pinfunction "1_1") (pintype "passive"))
      (node (ref "L3") (pin "2") (pinfunction "2_2") (pintype "passive"))
      (node (ref "U2") (pin "1") (pinfunction "+VIN_1") (pintype "passive"))
    )
    (net (code "69") (name "Net-(U2-+VOUT)") (class "Default")
      (node (ref "C2") (pin "1") (pinfunction "1_1") (pintype "passive"))
      (node (ref "F2") (pin "1") (pinfunction "1_1") (pintype "passive"))
      (node (ref "U2") (pin "3") (pinfunction "+VOUT_3") (pintype "passive"))
    )
    (net (code "70") (name "Net-(U3-+VIN)") (class "Default")
      (node (ref "C7") (pin "1") (pinfunction "1_1") (pintype "passive"))
      (node (ref "L5") (pin "2") (pinfunction "2_2") (pintype "passive"))
      (node (ref "U3") (pin "1") (pinfunction "+VIN_1") (pintype "passive"))
    )
    (net (code "71") (name "Net-(U3-+VOUT)") (class "Default")
      (node (ref "C8") (pin "1") (pinfunction "1_1") (pintype "passive"))
      (node (ref "F3") (pin "1") (pinfunction "1_1") (pintype "passive"))
      (node (ref "U3") (pin "3") (pinfunction "+VOUT_3") (pintype "passive"))
    )
    (net (code "72") (name "Net-(U4-IN-)") (class "Default")
      (node (ref "R7") (pin "2") (pinfunction "2_2") (pintype "passive"))
      (node (ref "U4") (pin "1") (pinfunction "OUT_1") (pintype "output"))
      (node (ref "U4") (pin "4") (pinfunction "IN-_4") (pintype "tri_state"))
    )
    (net (code "73") (name "Net-(U5-IN+)") (class "Default")
      (node (ref "C10") (pin "2") (pinfunction "2_2") (pintype "passive"))
      (node (ref "R6") (pin "2") (pinfunction "2_2") (pintype "passive"))
      (node (ref "U5") (pin "3") (pinfunction "IN+_3") (pintype "tri_state"))
      (node (ref "U7") (pin "1") (pinfunction "OUT_1") (pintype "output"))
    )
    (net (code "74") (name "Net-(U5-IN-)") (class "Default")
      (node (ref "R8") (pin "2") (pinfunction "2_2") (pintype "passive"))
      (node (ref "U5") (pin "1") (pinfunction "OUT_1") (pintype "output"))
      (node (ref "U5") (pin "4") (pinfunction "IN-_4") (pintype "tri_state"))
    )
    (net (code "75") (name "Net-(U6-AN24{slash}PMD0{slash}RP80{slash}RE0)") (class "Default")
      (node (ref "R24") (pin "2") (pinfunction "2_2") (pintype "passive"))
      (node (ref "U6") (pin "93") (pinfunction "AN24/PMD0/RP80/RE0_93") (pintype "bidirectional"))
    )
    (net (code "76") (name "Net-(U7-IN+)") (class "Default")
      (node (ref "R10") (pin "1") (pinfunction "1_1") (pintype "passive"))
      (node (ref "U7") (pin "3") (pinfunction "IN+_3") (pintype "tri_state"))
    )
    (net (code "77") (name "Net-(U7-IN-)") (class "Default")
      (node (ref "C10") (pin "1") (pinfunction "1_1") (pintype "passive"))
      (node (ref "R13") (pin "2") (pinfunction "2_2") (pintype "passive"))
      (node (ref "U7") (pin "4") (pinfunction "IN-_4") (pintype "tri_state"))
    )
    (net (code "78") (name "Net-(U8-IN-)") (class "Default")
      (node (ref "R14") (pin "2") (pinfunction "2_2") (pintype "passive"))
      (node (ref "U8") (pin "1") (pinfunction "OUT_1") (pintype "output"))
      (node (ref "U8") (pin "4") (pinfunction "IN-_4") (pintype "tri_state"))
    )
    (net (code "79") (name "Net-(U9-IN-)") (class "Default")
      (node (ref "R17") (pin "2") (pinfunction "2_2") (pintype "passive"))
      (node (ref "U9") (pin "1") (pinfunction "OUT_1") (pintype "output"))
      (node (ref "U9") (pin "4") (pinfunction "IN-_4") (pintype "tri_state"))
    )
    (net (code "80") (name "Net-(U10-IN+)") (class "Default")
      (node (ref "C16") (pin "2") (pinfunction "2_2") (pintype "passive"))
      (node (ref "R16") (pin "2") (pinfunction "2_2") (pintype "passive"))
      (node (ref "U10") (pin "3") (pinfunction "IN+_3") (pintype "tri_state"))
      (node (ref "U11") (pin "1") (pinfunction "OUT_1") (pintype "output"))
    )
    (net (code "81") (name "Net-(U10-IN-)") (class "Default")
      (node (ref "R18") (pin "2") (pinfunction "2_2") (pintype "passive"))
      (node (ref "U10") (pin "1") (pinfunction "OUT_1") (pintype "output"))
      (node (ref "U10") (pin "4") (pinfunction "IN-_4") (pintype "tri_state"))
    )
    (net (code "82") (name "Net-(U11-IN+)") (class "Default")
      (node (ref "R19") (pin "1") (pinfunction "1_1") (pintype "passive"))
      (node (ref "U11") (pin "3") (pinfunction "IN+_3") (pintype "tri_state"))
    )
    (net (code "83") (name "Net-(U11-IN-)") (class "Default")
      (node (ref "C16") (pin "1") (pinfunction "1_1") (pintype "passive"))
      (node (ref "R23") (pin "2") (pinfunction "2_2") (pintype "passive"))
      (node (ref "U11") (pin "4") (pinfunction "IN-_4") (pintype "tri_state"))
    )
    (net (code "84") (name "Net-(U12-IN-)") (class "Default")
      (node (ref "R26") (pin "2") (pinfunction "2_2") (pintype "passive"))
      (node (ref "U12") (pin "1") (pinfunction "OUT_1") (pintype "output"))
      (node (ref "U12") (pin "4") (pinfunction "IN-_4") (pintype "tri_state"))
    )
    (net (code "85") (name "Net-(UC1-CANH)") (class "Default")
      (node (ref "CHB1") (pin "1") (pinfunction "1_1") (pintype "passive"))
      (node (ref "L1") (pin "3") (pinfunction "3_3") (pintype "passive"))
      (node (ref "UC1") (pin "7") (pinfunction "CANH_7") (pintype "passive"))
    )
    (net (code "86") (name "Net-(UC1-CANL)") (class "Default")
      (node (ref "CLB1") (pin "1") (pinfunction "1_1") (pintype "passive"))
      (node (ref "L1") (pin "2") (pinfunction "2_2") (pintype "passive"))
      (node (ref "UC1") (pin "6") (pinfunction "CANL_6") (pintype "passive"))
    )
    (net (code "87") (name "Net-(UC1-STBY)") (class "Default")
      (node (ref "R1") (pin "1") (pinfunction "1_1") (pintype "passive"))
      (node (ref "UC1") (pin "8") (pinfunction "STBY_8") (pintype "passive"))
    )
    (net (code "88") (name "Net-(UC2-CANH)") (class "Default")
      (node (ref "CHB4") (pin "1") (pinfunction "1_1") (pintype "passive"))
      (node (ref "L4") (pin "3") (pinfunction "3_3") (pintype "passive"))
      (node (ref "UC2") (pin "7") (pinfunction "CANH_7") (pintype "passive"))
    )
    (net (code "89") (name "Net-(UC2-CANL)") (class "Default")
      (node (ref "CLB4") (pin "1") (pinfunction "1_1") (pintype "passive"))
      (node (ref "L4") (pin "2") (pinfunction "2_2") (pintype "passive"))
      (node (ref "UC2") (pin "6") (pinfunction "CANL_6") (pintype "passive"))
    )
    (net (code "90") (name "Net-(UC2-STBY)") (class "Default")
      (node (ref "R2") (pin "1") (pinfunction "1_1") (pintype "passive"))
      (node (ref "UC2") (pin "8") (pinfunction "STBY_8") (pintype "passive"))
    )
    (net (code "91") (name "unconnected-(LTC1-INB-Pad8)") (class "Default")
      (node (ref "LTC1") (pin "8") (pinfunction "INB_8") (pintype "passive"))
    )
    (net (code "92") (name "unconnected-(LTC1-VOUTB-Pad3)") (class "Default")
      (node (ref "LTC1") (pin "3") (pinfunction "VOUTB_3") (pintype "passive"))
    )
    (net (code "93") (name "unconnected-(R37-CW-Pad3)") (class "Default")
      (node (ref "R37") (pin "3") (pinfunction "CW_3") (pintype "passive"))
    )
    (net (code "94") (name "unconnected-(R38-CW-Pad3)") (class "Default")
      (node (ref "R38") (pin "3") (pinfunction "CW_3") (pintype "passive"))
    )
    (net (code "95") (name "unconnected-(R39-CW-Pad3)") (class "Default")
      (node (ref "R39") (pin "3") (pinfunction "CW_3") (pintype "passive"))
    )
    (net (code "96") (name "unconnected-(R40-CW-Pad3)") (class "Default")
      (node (ref "R40") (pin "3") (pinfunction "CW_3") (pintype "passive"))
    )
    (net (code "97") (name "unconnected-(U6-AN2{slash}C2IN2-{slash}VMIO{slash}RPI34{slash}RB2-Pad23)") (class "Default")
      (node (ref "U6") (pin "23") (pinfunction "AN2/C2IN2-/VMIO/RPI34/RB2_23") (pintype "bidirectional"))
    )
    (net (code "98") (name "unconnected-(U6-AN3{slash}C2IN1+{slash}VPIO{slash}RPI35{slash}RB3-Pad22)") (class "Default")
      (node (ref "U6") (pin "22") (pinfunction "AN3/C2IN1+/VPIO/RPI35/RB3_22") (pintype "bidirectional"))
    )
    (net (code "99") (name "unconnected-(U6-AN4{slash}C1IN2-{slash}USBOEN{slash}RPI36{slash}RB4-Pad21)") (class "Default")
      (node (ref "U6") (pin "21") (pinfunction "AN4/C1IN2-/USBOEN/RPI36/RB4_21") (pintype "bidirectional"))
    )
    (net (code "100") (name "unconnected-(U6-AN5{slash}C1IN1+{slash}VBUSON{slash}VBUSST{slash}RPI37{slash}RB5-Pad20)") (class "Default")
      (node (ref "U6") (pin "20") (pinfunction "AN5/C1IN1+/VBUSON/VBUSST/RPI37/RB5_20") (pintype "bidirectional"))
    )
    (net (code "101") (name "unconnected-(U6-AN8{slash}PMA6{slash}RPI40{slash}RB8-Pad32)") (class "Default")
      (node (ref "U6") (pin "32") (pinfunction "AN8/PMA6/RPI40/RB8_32") (pintype "bidirectional"))
    )
    (net (code "102") (name "unconnected-(U6-AN12{slash}PMA11{slash}RPI44{slash}RB12-Pad41)") (class "Default")
      (node (ref "U6") (pin "41") (pinfunction "AN12/PMA11/RPI44/RB12_41") (pintype "bidirectional"))
    )
    (net (code "103") (name "unconnected-(U6-AN13{slash}PMA10{slash}RPI45{slash}RB13-Pad42)") (class "Default")
      (node (ref "U6") (pin "42") (pinfunction "AN13/PMA10/RPI45/RB13_42") (pintype "bidirectional"))
    )
    (net (code "104") (name "unconnected-(U6-AN16{slash}RPI49{slash}RC1-Pad6)") (class "Default")
      (node (ref "U6") (pin "6") (pinfunction "AN16/RPI49/RC1_6") (pintype "bidirectional"))
    )
    (net (code "105") (name "unconnected-(U6-AN17{slash}RPI50{slash}RC2-Pad7)") (class "Default")
      (node (ref "U6") (pin "7") (pinfunction "AN17/RPI50/RC2_7") (pintype "bidirectional"))
    )
    (net (code "106") (name "unconnected-(U6-AN18{slash}RPI51{slash}RC3-Pad8)") (class "Default")
      (node (ref "U6") (pin "8") (pinfunction "AN18/RPI51/RC3_8") (pintype "bidirectional"))
    )
    (net (code "107") (name "unconnected-(U6-AN19{slash}RPI52{slash}RC4-Pad9)") (class "Default")
      (node (ref "U6") (pin "9") (pinfunction "AN19/RPI52/RC4_9") (pintype "bidirectional"))
    )
    (net (code "108") (name "unconnected-(U6-AN21{slash}RPI89{slash}RE9-Pad19)") (class "Default")
      (node (ref "U6") (pin "19") (pinfunction "AN21/RPI89/RE9_19") (pintype "bidirectional"))
    )
    (net (code "109") (name "unconnected-(U6-AN23{slash}RPI23{slash}RA7-Pad92)") (class "Default")
      (node (ref "U6") (pin "92") (pinfunction "AN23/RPI23/RA7_92") (pintype "bidirectional"))
    )
    (net (code "110") (name "unconnected-(U6-ASCL1{slash}PMCS2{slash}RPI74{slash}RD10-Pad70)") (class "Default")
      (node (ref "U6") (pin "70") (pinfunction "ASCL1/PMCS2/RPI74/RD10_70") (pintype "bidirectional"))
    )
    (net (code "111") (name "unconnected-(U6-ASCL2{slash}RPI18{slash}RA2-Pad58)") (class "Default")
      (node (ref "U6") (pin "58") (pinfunction "ASCL2/RPI18/RA2_58") (pintype "bidirectional"))
    )
    (net (code "112") (name "unconnected-(U6-ASDA1{slash}DPLN{slash}RPI73{slash}RD9-Pad69)") (class "Default")
      (node (ref "U6") (pin "69") (pinfunction "ASDA1/DPLN/RPI73/RD9_69") (pintype "bidirectional"))
    )
    (net (code "113") (name "unconnected-(U6-ASDA2{slash}RPI19{slash}RA3-Pad59)") (class "Default")
      (node (ref "U6") (pin "59") (pinfunction "ASDA2/RPI19/RA3_59") (pintype "bidirectional"))
    )
    (net (code "114") (name "unconnected-(U6-C1IN1-{slash}SDI2{slash}PMA4{slash}RPI119{slash}RG7-Pad11)") (class "Default")
      (node (ref "U6") (pin "11") (pinfunction "C1IN1-/SDI2/PMA4/RPI119/RG7_11") (pintype "bidirectional"))
    )
    (net (code "115") (name "unconnected-(U6-C1IN3-{slash}SCK2{slash}PMA5{slash}RP118{slash}RG6-Pad10)") (class "Default")
      (node (ref "U6") (pin "10") (pinfunction "C1IN3-/SCK2/PMA5/RP118/RG6_10") (pintype "bidirectional"))
    )
    (net (code "116") (name "unconnected-(U6-C2IN1-{slash}PMA2{slash}RPI121{slash}RG9-Pad14)") (class "Default")
      (node (ref "U6") (pin "14") (pinfunction "C2IN1-/PMA2/RPI121/RG9_14") (pintype "bidirectional"))
    )
    (net (code "117") (name "unconnected-(U6-C2IN3-{slash}SDO2{slash}PMA3{slash}RP120{slash}RG8-Pad12)") (class "Default")
      (node (ref "U6") (pin "12") (pinfunction "C2IN3-/SDO2/PMA3/RP120/RG8_12") (pintype "bidirectional"))
    )
    (net (code "118") (name "unconnected-(U6-C3IN1+{slash}VCMPST3{slash}RP71{slash}RD7-Pad84)") (class "Default")
      (node (ref "U6") (pin "84") (pinfunction "C3IN1+/VCMPST3/RP71/RD7_84") (pintype "bidirectional"))
    )
    (net (code "119") (name "unconnected-(U6-C3IN2-{slash}RP70{slash}RD6-Pad83)") (class "Default")
      (node (ref "U6") (pin "83") (pinfunction "C3IN2-/RP70/RD6_83") (pintype "bidirectional"))
    )
    (net (code "120") (name "unconnected-(U6-D+{slash}RG2-Pad57)") (class "Default")
      (node (ref "U6") (pin "57") (pinfunction "D+/RG2_57") (pintype "input"))
    )
    (net (code "121") (name "unconnected-(U6-D-{slash}RG3-Pad56)") (class "Default")
      (node (ref "U6") (pin "56") (pinfunction "D-/RG3_56") (pintype "input"))
    )
    (net (code "122") (name "unconnected-(U6-DPH{slash}RP66{slash}RD2-Pad77)") (class "Default")
      (node (ref "U6") (pin "77") (pinfunction "DPH/RP66/RD2_77") (pintype "bidirectional"))
    )
    (net (code "123") (name "unconnected-(U6-INT0{slash}DMH{slash}RP64{slash}RD0-Pad72)") (class "Default")
      (node (ref "U6") (pin "72") (pinfunction "INT0/DMH/RP64/RD0_72") (pintype "bidirectional"))
    )
    (net (code "124") (name "unconnected-(U6-PGEC2{slash}SOSCO{slash}C3IN1-{slash}T1CK{slash}RPI62{slash}RC14-Pad74)") (class "Default")
      (node (ref "U6") (pin "74") (pinfunction "PGEC2/SOSCO/C3IN1-/T1CK/RPI62/RC14_74") (pintype "bidirectional"))
    )
    (net (code "125") (name "unconnected-(U6-PGEC3{slash}AN1{slash}RPI33{slash}RB1-Pad24)") (class "Default")
      (node (ref "U6") (pin "24") (pinfunction "PGEC3/AN1/RPI33/RB1_24") (pintype "bidirectional"))
    )
    (net (code "126") (name "unconnected-(U6-PGED2{slash}SOSCI{slash}C3IN3-{slash}RPI61{slash}RC13-Pad73)") (class "Default")
      (node (ref "U6") (pin "73") (pinfunction "PGED2/SOSCI/C3IN3-/RPI61/RC13_73") (pintype "bidirectional"))
    )
    (net (code "127") (name "unconnected-(U6-PGED3{slash}AN0{slash}RPI32{slash}RB0-Pad25)") (class "Default")
      (node (ref "U6") (pin "25") (pinfunction "PGED3/AN0/RPI32/RB0_25") (pintype "bidirectional"))
    )
    (net (code "128") (name "unconnected-(U6-PMBE{slash}RP67{slash}RD3-Pad78)") (class "Default")
      (node (ref "U6") (pin "78") (pinfunction "PMBE/RP67/RD3_78") (pintype "bidirectional"))
    )
    (net (code "129") (name "unconnected-(U6-PMCS1{slash}RPI75{slash}RD11-Pad71)") (class "Default")
      (node (ref "U6") (pin "71") (pinfunction "PMCS1/RPI75/RD11_71") (pintype "bidirectional"))
    )
    (net (code "130") (name "unconnected-(U6-PMRD{slash}RP69{slash}RD5-Pad82)") (class "Default")
      (node (ref "U6") (pin "82") (pinfunction "PMRD/RP69/RD5_82") (pintype "bidirectional"))
    )
    (net (code "131") (name "unconnected-(U6-RP79{slash}RD15-Pad48)") (class "Default")
      (node (ref "U6") (pin "48") (pinfunction "RP79/RD15_48") (pintype "bidirectional"))
    )
    (net (code "132") (name "unconnected-(U6-RP98{slash}RF2-Pad52)") (class "Default")
      (node (ref "U6") (pin "52") (pinfunction "RP98/RF2_52") (pintype "bidirectional"))
    )
    (net (code "133") (name "unconnected-(U6-RP104{slash}RF8-Pad53)") (class "Default")
      (node (ref "U6") (pin "53") (pinfunction "RP104/RF8_53") (pintype "bidirectional"))
    )
    (net (code "134") (name "unconnected-(U6-RP108{slash}RF12-Pad40)") (class "Default")
      (node (ref "U6") (pin "40") (pinfunction "RP108/RF12_40") (pintype "bidirectional"))
    )
    (net (code "135") (name "unconnected-(U6-RP109{slash}RF13-Pad39)") (class "Default")
      (node (ref "U6") (pin "39") (pinfunction "RP109/RF13_39") (pintype "bidirectional"))
    )
    (net (code "136") (name "unconnected-(U6-RP113{slash}RG1-Pad89)") (class "Default")
      (node (ref "U6") (pin "89") (pinfunction "RP113/RG1_89") (pintype "bidirectional"))
    )
    (net (code "137") (name "unconnected-(U6-RP125{slash}RG13-Pad97)") (class "Default")
      (node (ref "U6") (pin "97") (pinfunction "RP125/RG13_97") (pintype "bidirectional"))
    )
    (net (code "138") (name "unconnected-(U6-RP126{slash}RG14-Pad95)") (class "Default")
      (node (ref "U6") (pin "95") (pinfunction "RP126/RG14_95") (pintype "bidirectional"))
    )
    (net (code "139") (name "unconnected-(U6-RP127{slash}RG15-Pad1)") (class "Default")
      (node (ref "U6") (pin "1") (pinfunction "RP127/RG15_1") (pintype "bidirectional"))
    )
    (net (code "140") (name "unconnected-(U6-RPI30{slash}RA14-Pad66)") (class "Default")
      (node (ref "U6") (pin "66") (pinfunction "RPI30/RA14_66") (pintype "bidirectional"))
    )
    (net (code "141") (name "unconnected-(U6-RPI31{slash}RA15-Pad67)") (class "Default")
      (node (ref "U6") (pin "67") (pinfunction "RPI31/RA15_67") (pintype "bidirectional"))
    )
    (net (code "142") (name "unconnected-(U6-RPI76{slash}RD12-Pad79)") (class "Default")
      (node (ref "U6") (pin "79") (pinfunction "RPI76/RD12_79") (pintype "bidirectional"))
    )
    (net (code "143") (name "unconnected-(U6-RPI78{slash}RD14-Pad47)") (class "Default")
      (node (ref "U6") (pin "47") (pinfunction "RPI78/RD14_47") (pintype "bidirectional"))
    )
    (net (code "144") (name "unconnected-(U6-RPI124{slash}RG12-Pad96)") (class "Default")
      (node (ref "U6") (pin "96") (pinfunction "RPI124/RG12_96") (pintype "bidirectional"))
    )
    (net (code "145") (name "unconnected-(U6-RTCC{slash}DMLN{slash}RPI72{slash}RD8-Pad68)") (class "Default")
      (node (ref "U6") (pin "68") (pinfunction "RTCC/DMLN/RPI72/RD8_68") (pintype "bidirectional"))
    )
    (net (code "146") (name "unconnected-(U6-SCL2{slash}PMA8{slash}RP101{slash}RF5-Pad50)") (class "Default")
      (node (ref "U6") (pin "50") (pinfunction "SCL2/PMA8/RP101/RF5_50") (pintype "bidirectional"))
    )
    (net (code "147") (name "unconnected-(U6-SDA2{slash}PMA9{slash}RP100{slash}RF4-Pad49)") (class "Default")
      (node (ref "U6") (pin "49") (pinfunction "SDA2/PMA9/RP100/RF4_49") (pintype "bidirectional"))
    )
    (net (code "148") (name "unconnected-(U6-TCK{slash}RPI17{slash}RA1-Pad38)") (class "Default")
      (node (ref "U6") (pin "38") (pinfunction "TCK/RPI17/RA1_38") (pintype "bidirectional"))
    )
    (net (code "149") (name "unconnected-(U6-TDI{slash}RPI20{slash}RA4-Pad60)") (class "Default")
      (node (ref "U6") (pin "60") (pinfunction "TDI/RPI20/RA4_60") (pintype "bidirectional"))
    )
    (net (code "150") (name "unconnected-(U6-TDO{slash}RPI21{slash}RA5-Pad61)") (class "Default")
      (node (ref "U6") (pin "61") (pinfunction "TDO/RPI21/RA5_61") (pintype "bidirectional"))
    )
    (net (code "151") (name "unconnected-(U6-TMS{slash}RPI16{slash}RA0-Pad17)") (class "Default")
      (node (ref "U6") (pin "17") (pinfunction "TMS/RPI16/RA0_17") (pintype "bidirectional"))
    )
    (net (code "152") (name "unconnected-(U6-USBID{slash}RP99{slash}RF3-Pad51)") (class "Default")
      (node (ref "U6") (pin "51") (pinfunction "USBID/RP99/RF3_51") (pintype "bidirectional"))
    )
    (net (code "153") (name "unconnected-(U6-VBUS-Pad54)") (class "Default")
      (node (ref "U6") (pin "54") (pinfunction "VBUS_54") (pintype "input"))
    )
    (net (code "154") (name "unconnected-(U6-VCMPST1{slash}RP96{slash}RF0-Pad87)") (class "Default")
      (node (ref "U6") (pin "87") (pinfunction "VCMPST1/RP96/RF0_87") (pintype "bidirectional"))
    )
    (net (code "155") (name "unconnected-(U6-VCMPST2{slash}RP97{slash}RF1-Pad88)") (class "Default")
      (node (ref "U6") (pin "88") (pinfunction "VCMPST2/RP97/RF1_88") (pintype "bidirectional"))
    )
    (net (code "156") (name "unconnected-(U6-VCPCON{slash}RP65{slash}RD1-Pad76)") (class "Default")
      (node (ref "U6") (pin "76") (pinfunction "VCPCON/RP65/RD1_76") (pintype "bidirectional"))
    )
    (net (code "157") (name "unconnected-(U6-VREF+{slash}RA10-Pad29)") (class "Default")
      (node (ref "U6") (pin "29") (pinfunction "VREF+/RA10_29") (pintype "bidirectional"))
    )
    (net (code "158") (name "unconnected-(U6-VREF-{slash}RA9-Pad28)") (class "Default")
      (node (ref "U6") (pin "28") (pinfunction "VREF-/RA9_28") (pintype "bidirectional"))
    )
    (net (code "159") (name "unconnected-(U6-VUSB-Pad55)") (class "Default")
      (node (ref "U6") (pin "55") (pinfunction "VUSB_55") (pintype "power_in"))
    )
  )
)
